# bridge-1A.net
KiCad netlist of a schematic drawn in EAGLE
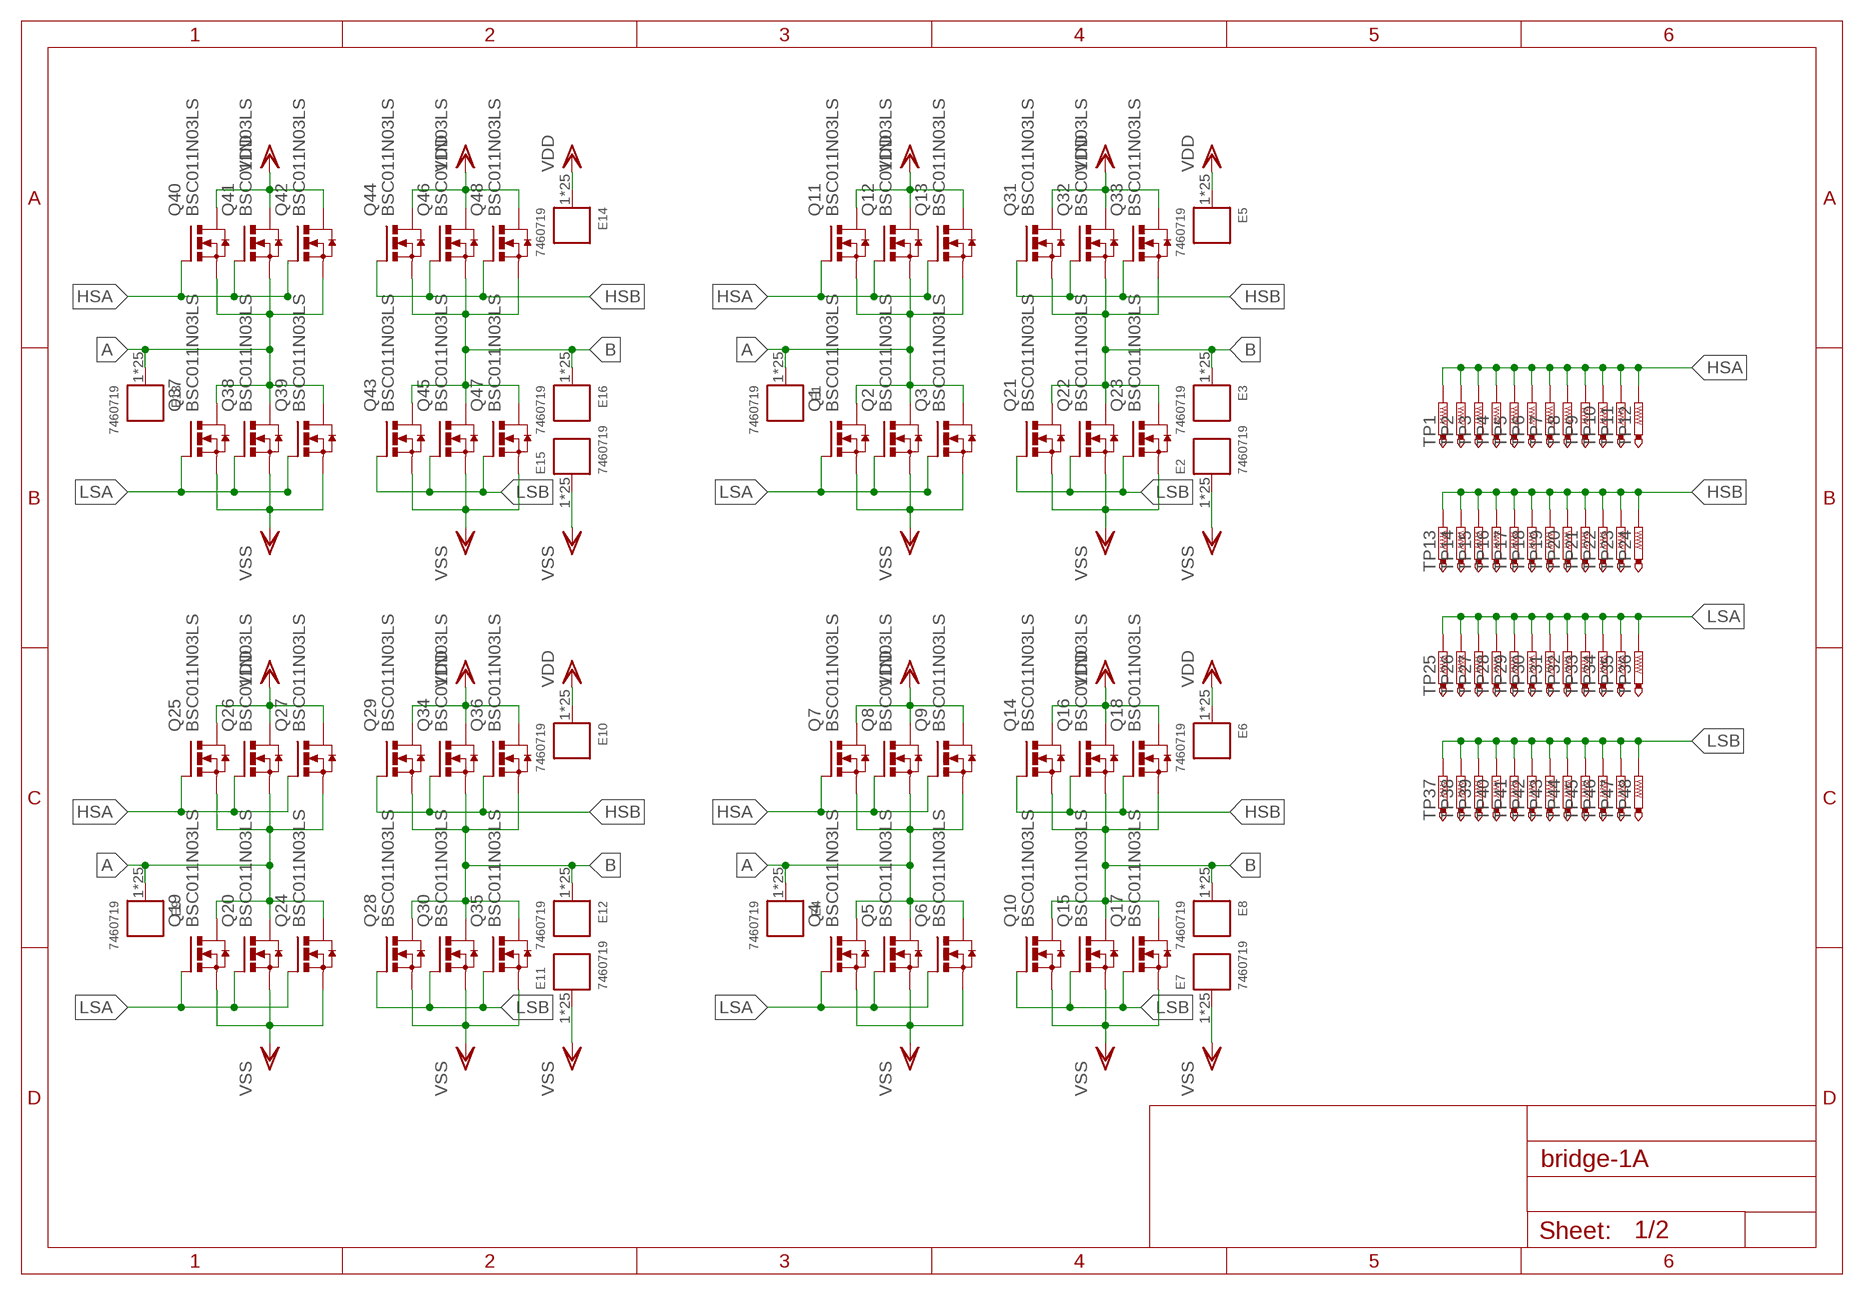
[diagram p0: schematic, sheet 1]

(export (version "E")
  (design (tool "Eeschema 10.0.6"))
  (components
    (comp (ref "E1")
      (value "7460719")
      (footprint "eagle-import:25PINS_FULL_HAL")
      (fields (field (name "MFG") "WUERTHELEKTRONIK"))
      (libsource (lib "eagle-import") (part "WP-SHFU_K(HAL)"))
    )
    (comp (ref "E2")
      (value "7460719")
      (footprint "eagle-import:25PINS_FULL_HAL")
      (fields (field (name "MFG") "WUERTHELEKTRONIK"))
      (libsource (lib "eagle-import") (part "WP-SHFU_K(HAL)"))
    )
    (comp (ref "E3")
      (value "7460719")
      (footprint "eagle-import:25PINS_FULL_HAL")
      (fields (field (name "MFG") "WUERTHELEKTRONIK"))
      (libsource (lib "eagle-import") (part "WP-SHFU_K(HAL)"))
    )
    (comp (ref "E4")
      (value "7460719")
      (footprint "eagle-import:25PINS_FULL_HAL")
      (fields (field (name "MFG") "WUERTHELEKTRONIK"))
      (libsource (lib "eagle-import") (part "WP-SHFU_K(HAL)"))
    )
    (comp (ref "E5")
      (value "7460719")
      (footprint "eagle-import:25PINS_FULL_HAL")
      (fields (field (name "MFG") "WUERTHELEKTRONIK"))
      (libsource (lib "eagle-import") (part "WP-SHFU_K(HAL)"))
    )
    (comp (ref "E6")
      (value "7460719")
      (footprint "eagle-import:25PINS_FULL_HAL")
      (fields (field (name "MFG") "WUERTHELEKTRONIK"))
      (libsource (lib "eagle-import") (part "WP-SHFU_K(HAL)"))
    )
    (comp (ref "E7")
      (value "7460719")
      (footprint "eagle-import:25PINS_FULL_HAL")
      (fields (field (name "MFG") "WUERTHELEKTRONIK"))
      (libsource (lib "eagle-import") (part "WP-SHFU_K(HAL)"))
    )
    (comp (ref "E8")
      (value "7460719")
      (footprint "eagle-import:25PINS_FULL_HAL")
      (fields (field (name "MFG") "WUERTHELEKTRONIK"))
      (libsource (lib "eagle-import") (part "WP-SHFU_K(HAL)"))
    )
    (comp (ref "E9")
      (value "7460719")
      (footprint "eagle-import:25PINS_FULL_HAL")
      (fields (field (name "MFG") "WUERTHELEKTRONIK"))
      (libsource (lib "eagle-import") (part "WP-SHFU_K(HAL)"))
    )
    (comp (ref "E10")
      (value "7460719")
      (footprint "eagle-import:25PINS_FULL_HAL")
      (fields (field (name "MFG") "WUERTHELEKTRONIK"))
      (libsource (lib "eagle-import") (part "WP-SHFU_K(HAL)"))
    )
    (comp (ref "E11")
      (value "7460719")
      (footprint "eagle-import:25PINS_FULL_HAL")
      (fields (field (name "MFG") "WUERTHELEKTRONIK"))
      (libsource (lib "eagle-import") (part "WP-SHFU_K(HAL)"))
    )
    (comp (ref "E12")
      (value "7460719")
      (footprint "eagle-import:25PINS_FULL_HAL")
      (fields (field (name "MFG") "WUERTHELEKTRONIK"))
      (libsource (lib "eagle-import") (part "WP-SHFU_K(HAL)"))
    )
    (comp (ref "E13")
      (value "7460719")
      (footprint "eagle-import:25PINS_FULL_HAL")
      (fields (field (name "MFG") "WUERTHELEKTRONIK"))
      (libsource (lib "eagle-import") (part "WP-SHFU_K(HAL)"))
    )
    (comp (ref "E14")
      (value "7460719")
      (footprint "eagle-import:25PINS_FULL_HAL")
      (fields (field (name "MFG") "WUERTHELEKTRONIK"))
      (libsource (lib "eagle-import") (part "WP-SHFU_K(HAL)"))
    )
    (comp (ref "E15")
      (value "7460719")
      (footprint "eagle-import:25PINS_FULL_HAL")
      (fields (field (name "MFG") "WUERTHELEKTRONIK"))
      (libsource (lib "eagle-import") (part "WP-SHFU_K(HAL)"))
    )
    (comp (ref "E16")
      (value "7460719")
      (footprint "eagle-import:25PINS_FULL_HAL")
      (fields (field (name "MFG") "WUERTHELEKTRONIK"))
      (libsource (lib "eagle-import") (part "WP-SHFU_K(HAL)"))
    )
    (comp (ref "Q1")
      (value "BSC011N03LS")
      (footprint "eagle-import:PG-TDSON-8")
      (libsource (lib "eagle-import") (part "BSC011N03LS"))
    )
    (comp (ref "Q2")
      (value "BSC011N03LS")
      (footprint "eagle-import:PG-TDSON-8")
      (libsource (lib "eagle-import") (part "BSC011N03LS"))
    )
    (comp (ref "Q3")
      (value "BSC011N03LS")
      (footprint "eagle-import:PG-TDSON-8")
      (libsource (lib "eagle-import") (part "BSC011N03LS"))
    )
    (comp (ref "Q4")
      (value "BSC011N03LS")
      (footprint "eagle-import:PG-TDSON-8")
      (libsource (lib "eagle-import") (part "BSC011N03LS"))
    )
    (comp (ref "Q5")
      (value "BSC011N03LS")
      (footprint "eagle-import:PG-TDSON-8")
      (libsource (lib "eagle-import") (part "BSC011N03LS"))
    )
    (comp (ref "Q6")
      (value "BSC011N03LS")
      (footprint "eagle-import:PG-TDSON-8")
      (libsource (lib "eagle-import") (part "BSC011N03LS"))
    )
    (comp (ref "Q7")
      (value "BSC011N03LS")
      (footprint "eagle-import:PG-TDSON-8")
      (libsource (lib "eagle-import") (part "BSC011N03LS"))
    )
    (comp (ref "Q8")
      (value "BSC011N03LS")
      (footprint "eagle-import:PG-TDSON-8")
      (libsource (lib "eagle-import") (part "BSC011N03LS"))
    )
    (comp (ref "Q9")
      (value "BSC011N03LS")
      (footprint "eagle-import:PG-TDSON-8")
      (libsource (lib "eagle-import") (part "BSC011N03LS"))
    )
    (comp (ref "Q10")
      (value "BSC011N03LS")
      (footprint "eagle-import:PG-TDSON-8")
      (libsource (lib "eagle-import") (part "BSC011N03LS"))
    )
    (comp (ref "Q11")
      (value "BSC011N03LS")
      (footprint "eagle-import:PG-TDSON-8")
      (libsource (lib "eagle-import") (part "BSC011N03LS"))
    )
    (comp (ref "Q12")
      (value "BSC011N03LS")
      (footprint "eagle-import:PG-TDSON-8")
      (libsource (lib "eagle-import") (part "BSC011N03LS"))
    )
    (comp (ref "Q13")
      (value "BSC011N03LS")
      (footprint "eagle-import:PG-TDSON-8")
      (libsource (lib "eagle-import") (part "BSC011N03LS"))
    )
    (comp (ref "Q14")
      (value "BSC011N03LS")
      (footprint "eagle-import:PG-TDSON-8")
      (libsource (lib "eagle-import") (part "BSC011N03LS"))
    )
    (comp (ref "Q15")
      (value "BSC011N03LS")
      (footprint "eagle-import:PG-TDSON-8")
      (libsource (lib "eagle-import") (part "BSC011N03LS"))
    )
    (comp (ref "Q16")
      (value "BSC011N03LS")
      (footprint "eagle-import:PG-TDSON-8")
      (libsource (lib "eagle-import") (part "BSC011N03LS"))
    )
    (comp (ref "Q17")
      (value "BSC011N03LS")
      (footprint "eagle-import:PG-TDSON-8")
      (libsource (lib "eagle-import") (part "BSC011N03LS"))
    )
    (comp (ref "Q18")
      (value "BSC011N03LS")
      (footprint "eagle-import:PG-TDSON-8")
      (libsource (lib "eagle-import") (part "BSC011N03LS"))
    )
    (comp (ref "Q19")
      (value "BSC011N03LS")
      (footprint "eagle-import:PG-TDSON-8")
      (libsource (lib "eagle-import") (part "BSC011N03LS"))
    )
    (comp (ref "Q20")
      (value "BSC011N03LS")
      (footprint "eagle-import:PG-TDSON-8")
      (libsource (lib "eagle-import") (part "BSC011N03LS"))
    )
    (comp (ref "Q21")
      (value "BSC011N03LS")
      (footprint "eagle-import:PG-TDSON-8")
      (libsource (lib "eagle-import") (part "BSC011N03LS"))
    )
    (comp (ref "Q22")
      (value "BSC011N03LS")
      (footprint "eagle-import:PG-TDSON-8")
      (libsource (lib "eagle-import") (part "BSC011N03LS"))
    )
    (comp (ref "Q23")
      (value "BSC011N03LS")
      (footprint "eagle-import:PG-TDSON-8")
      (libsource (lib "eagle-import") (part "BSC011N03LS"))
    )
    (comp (ref "Q24")
      (value "BSC011N03LS")
      (footprint "eagle-import:PG-TDSON-8")
      (libsource (lib "eagle-import") (part "BSC011N03LS"))
    )
    (comp (ref "Q25")
      (value "BSC011N03LS")
      (footprint "eagle-import:PG-TDSON-8")
      (libsource (lib "eagle-import") (part "BSC011N03LS"))
    )
    (comp (ref "Q26")
      (value "BSC011N03LS")
      (footprint "eagle-import:PG-TDSON-8")
      (libsource (lib "eagle-import") (part "BSC011N03LS"))
    )
    (comp (ref "Q27")
      (value "BSC011N03LS")
      (footprint "eagle-import:PG-TDSON-8")
      (libsource (lib "eagle-import") (part "BSC011N03LS"))
    )
    (comp (ref "Q28")
      (value "BSC011N03LS")
      (footprint "eagle-import:PG-TDSON-8")
      (libsource (lib "eagle-import") (part "BSC011N03LS"))
    )
    (comp (ref "Q29")
      (value "BSC011N03LS")
      (footprint "eagle-import:PG-TDSON-8")
      (libsource (lib "eagle-import") (part "BSC011N03LS"))
    )
    (comp (ref "Q30")
      (value "BSC011N03LS")
      (footprint "eagle-import:PG-TDSON-8")
      (libsource (lib "eagle-import") (part "BSC011N03LS"))
    )
    (comp (ref "Q31")
      (value "BSC011N03LS")
      (footprint "eagle-import:PG-TDSON-8")
      (libsource (lib "eagle-import") (part "BSC011N03LS"))
    )
    (comp (ref "Q32")
      (value "BSC011N03LS")
      (footprint "eagle-import:PG-TDSON-8")
      (libsource (lib "eagle-import") (part "BSC011N03LS"))
    )
    (comp (ref "Q33")
      (value "BSC011N03LS")
      (footprint "eagle-import:PG-TDSON-8")
      (libsource (lib "eagle-import") (part "BSC011N03LS"))
    )
    (comp (ref "Q34")
      (value "BSC011N03LS")
      (footprint "eagle-import:PG-TDSON-8")
      (libsource (lib "eagle-import") (part "BSC011N03LS"))
    )
    (comp (ref "Q35")
      (value "BSC011N03LS")
      (footprint "eagle-import:PG-TDSON-8")
      (libsource (lib "eagle-import") (part "BSC011N03LS"))
    )
    (comp (ref "Q36")
      (value "BSC011N03LS")
      (footprint "eagle-import:PG-TDSON-8")
      (libsource (lib "eagle-import") (part "BSC011N03LS"))
    )
    (comp (ref "Q37")
      (value "BSC011N03LS")
      (footprint "eagle-import:PG-TDSON-8")
      (libsource (lib "eagle-import") (part "BSC011N03LS"))
    )
    (comp (ref "Q38")
      (value "BSC011N03LS")
      (footprint "eagle-import:PG-TDSON-8")
      (libsource (lib "eagle-import") (part "BSC011N03LS"))
    )
    (comp (ref "Q39")
      (value "BSC011N03LS")
      (footprint "eagle-import:PG-TDSON-8")
      (libsource (lib "eagle-import") (part "BSC011N03LS"))
    )
    (comp (ref "Q40")
      (value "BSC011N03LS")
      (footprint "eagle-import:PG-TDSON-8")
      (libsource (lib "eagle-import") (part "BSC011N03LS"))
    )
    (comp (ref "Q41")
      (value "BSC011N03LS")
      (footprint "eagle-import:PG-TDSON-8")
      (libsource (lib "eagle-import") (part "BSC011N03LS"))
    )
    (comp (ref "Q42")
      (value "BSC011N03LS")
      (footprint "eagle-import:PG-TDSON-8")
      (libsource (lib "eagle-import") (part "BSC011N03LS"))
    )
    (comp (ref "Q43")
      (value "BSC011N03LS")
      (footprint "eagle-import:PG-TDSON-8")
      (libsource (lib "eagle-import") (part "BSC011N03LS"))
    )
    (comp (ref "Q44")
      (value "BSC011N03LS")
      (footprint "eagle-import:PG-TDSON-8")
      (libsource (lib "eagle-import") (part "BSC011N03LS"))
    )
    (comp (ref "Q45")
      (value "BSC011N03LS")
      (footprint "eagle-import:PG-TDSON-8")
      (libsource (lib "eagle-import") (part "BSC011N03LS"))
    )
    (comp (ref "Q46")
      (value "BSC011N03LS")
      (footprint "eagle-import:PG-TDSON-8")
      (libsource (lib "eagle-import") (part "BSC011N03LS"))
    )
    (comp (ref "Q47")
      (value "BSC011N03LS")
      (footprint "eagle-import:PG-TDSON-8")
      (libsource (lib "eagle-import") (part "BSC011N03LS"))
    )
    (comp (ref "Q48")
      (value "BSC011N03LS")
      (footprint "eagle-import:PG-TDSON-8")
      (libsource (lib "eagle-import") (part "BSC011N03LS"))
    )
    (comp (ref "TP1")
      (value "PTR1TP12SQ")
      (footprint "eagle-import:TP12SQ")
      (libsource (lib "eagle-import") (part "PTR1TP12SQ"))
    )
    (comp (ref "TP2")
      (value "PTR1TP12SQ")
      (footprint "eagle-import:TP12SQ")
      (libsource (lib "eagle-import") (part "PTR1TP12SQ"))
    )
    (comp (ref "TP3")
      (value "PTR1TP12SQ")
      (footprint "eagle-import:TP12SQ")
      (libsource (lib "eagle-import") (part "PTR1TP12SQ"))
    )
    (comp (ref "TP4")
      (value "PTR1TP12SQ")
      (footprint "eagle-import:TP12SQ")
      (libsource (lib "eagle-import") (part "PTR1TP12SQ"))
    )
    (comp (ref "TP5")
      (value "PTR1TP12SQ")
      (footprint "eagle-import:TP12SQ")
      (libsource (lib "eagle-import") (part "PTR1TP12SQ"))
    )
    (comp (ref "TP6")
      (value "PTR1TP12SQ")
      (footprint "eagle-import:TP12SQ")
      (libsource (lib "eagle-import") (part "PTR1TP12SQ"))
    )
    (comp (ref "TP7")
      (value "PTR1TP12SQ")
      (footprint "eagle-import:TP12SQ")
      (libsource (lib "eagle-import") (part "PTR1TP12SQ"))
    )
    (comp (ref "TP8")
      (value "PTR1TP12SQ")
      (footprint "eagle-import:TP12SQ")
      (libsource (lib "eagle-import") (part "PTR1TP12SQ"))
    )
    (comp (ref "TP9")
      (value "PTR1TP12SQ")
      (footprint "eagle-import:TP12SQ")
      (libsource (lib "eagle-import") (part "PTR1TP12SQ"))
    )
    (comp (ref "TP10")
      (value "PTR1TP12SQ")
      (footprint "eagle-import:TP12SQ")
      (libsource (lib "eagle-import") (part "PTR1TP12SQ"))
    )
    (comp (ref "TP11")
      (value "PTR1TP12SQ")
      (footprint "eagle-import:TP12SQ")
      (libsource (lib "eagle-import") (part "PTR1TP12SQ"))
    )
    (comp (ref "TP12")
      (value "PTR1TP12SQ")
      (footprint "eagle-import:TP12SQ")
      (libsource (lib "eagle-import") (part "PTR1TP12SQ"))
    )
    (comp (ref "TP13")
      (value "PTR1TP12SQ")
      (footprint "eagle-import:TP12SQ")
      (libsource (lib "eagle-import") (part "PTR1TP12SQ"))
    )
    (comp (ref "TP14")
      (value "PTR1TP12SQ")
      (footprint "eagle-import:TP12SQ")
      (libsource (lib "eagle-import") (part "PTR1TP12SQ"))
    )
    (comp (ref "TP15")
      (value "PTR1TP12SQ")
      (footprint "eagle-import:TP12SQ")
      (libsource (lib "eagle-import") (part "PTR1TP12SQ"))
    )
    (comp (ref "TP16")
      (value "PTR1TP12SQ")
      (footprint "eagle-import:TP12SQ")
      (libsource (lib "eagle-import") (part "PTR1TP12SQ"))
    )
    (comp (ref "TP17")
      (value "PTR1TP12SQ")
      (footprint "eagle-import:TP12SQ")
      (libsource (lib "eagle-import") (part "PTR1TP12SQ"))
    )
    (comp (ref "TP18")
      (value "PTR1TP12SQ")
      (footprint "eagle-import:TP12SQ")
      (libsource (lib "eagle-import") (part "PTR1TP12SQ"))
    )
    (comp (ref "TP19")
      (value "PTR1TP12SQ")
      (footprint "eagle-import:TP12SQ")
      (libsource (lib "eagle-import") (part "PTR1TP12SQ"))
    )
    (comp (ref "TP20")
      (value "PTR1TP12SQ")
      (footprint "eagle-import:TP12SQ")
      (libsource (lib "eagle-import") (part "PTR1TP12SQ"))
    )
    (comp (ref "TP21")
      (value "PTR1TP12SQ")
      (footprint "eagle-import:TP12SQ")
      (libsource (lib "eagle-import") (part "PTR1TP12SQ"))
    )
    (comp (ref "TP22")
      (value "PTR1TP12SQ")
      (footprint "eagle-import:TP12SQ")
      (libsource (lib "eagle-import") (part "PTR1TP12SQ"))
    )
    (comp (ref "TP23")
      (value "PTR1TP12SQ")
      (footprint "eagle-import:TP12SQ")
      (libsource (lib "eagle-import") (part "PTR1TP12SQ"))
    )
    (comp (ref "TP24")
      (value "PTR1TP12SQ")
      (footprint "eagle-import:TP12SQ")
      (libsource (lib "eagle-import") (part "PTR1TP12SQ"))
    )
    (comp (ref "TP25")
      (value "PTR1TP12SQ")
      (footprint "eagle-import:TP12SQ")
      (libsource (lib "eagle-import") (part "PTR1TP12SQ"))
    )
    (comp (ref "TP26")
      (value "PTR1TP12SQ")
      (footprint "eagle-import:TP12SQ")
      (libsource (lib "eagle-import") (part "PTR1TP12SQ"))
    )
    (comp (ref "TP27")
      (value "PTR1TP12SQ")
      (footprint "eagle-import:TP12SQ")
      (libsource (lib "eagle-import") (part "PTR1TP12SQ"))
    )
    (comp (ref "TP28")
      (value "PTR1TP12SQ")
      (footprint "eagle-import:TP12SQ")
      (libsource (lib "eagle-import") (part "PTR1TP12SQ"))
    )
    (comp (ref "TP29")
      (value "PTR1TP12SQ")
      (footprint "eagle-import:TP12SQ")
      (libsource (lib "eagle-import") (part "PTR1TP12SQ"))
    )
    (comp (ref "TP30")
      (value "PTR1TP12SQ")
      (footprint "eagle-import:TP12SQ")
      (libsource (lib "eagle-import") (part "PTR1TP12SQ"))
    )
    (comp (ref "TP31")
      (value "PTR1TP12SQ")
      (footprint "eagle-import:TP12SQ")
      (libsource (lib "eagle-import") (part "PTR1TP12SQ"))
    )
    (comp (ref "TP32")
      (value "PTR1TP12SQ")
      (footprint "eagle-import:TP12SQ")
      (libsource (lib "eagle-import") (part "PTR1TP12SQ"))
    )
    (comp (ref "TP33")
      (value "PTR1TP12SQ")
      (footprint "eagle-import:TP12SQ")
      (libsource (lib "eagle-import") (part "PTR1TP12SQ"))
    )
    (comp (ref "TP34")
      (value "PTR1TP12SQ")
      (footprint "eagle-import:TP12SQ")
      (libsource (lib "eagle-import") (part "PTR1TP12SQ"))
    )
    (comp (ref "TP35")
      (value "PTR1TP12SQ")
      (footprint "eagle-import:TP12SQ")
      (libsource (lib "eagle-import") (part "PTR1TP12SQ"))
    )
    (comp (ref "TP36")
      (value "PTR1TP12SQ")
      (footprint "eagle-import:TP12SQ")
      (libsource (lib "eagle-import") (part "PTR1TP12SQ"))
    )
    (comp (ref "TP37")
      (value "PTR1TP12SQ")
      (footprint "eagle-import:TP12SQ")
      (libsource (lib "eagle-import") (part "PTR1TP12SQ"))
    )
    (comp (ref "TP38")
      (value "PTR1TP12SQ")
      (footprint "eagle-import:TP12SQ")
      (libsource (lib "eagle-import") (part "PTR1TP12SQ"))
    )
    (comp (ref "TP39")
      (value "PTR1TP12SQ")
      (footprint "eagle-import:TP12SQ")
      (libsource (lib "eagle-import") (part "PTR1TP12SQ"))
    )
    (comp (ref "TP40")
      (value "PTR1TP12SQ")
      (footprint "eagle-import:TP12SQ")
      (libsource (lib "eagle-import") (part "PTR1TP12SQ"))
    )
    (comp (ref "TP41")
      (value "PTR1TP12SQ")
      (footprint "eagle-import:TP12SQ")
      (libsource (lib "eagle-import") (part "PTR1TP12SQ"))
    )
    (comp (ref "TP42")
      (value "PTR1TP12SQ")
      (footprint "eagle-import:TP12SQ")
      (libsource (lib "eagle-import") (part "PTR1TP12SQ"))
    )
    (comp (ref "TP43")
      (value "PTR1TP12SQ")
      (footprint "eagle-import:TP12SQ")
      (libsource (lib "eagle-import") (part "PTR1TP12SQ"))
    )
    (comp (ref "TP44")
      (value "PTR1TP12SQ")
      (footprint "eagle-import:TP12SQ")
      (libsource (lib "eagle-import") (part "PTR1TP12SQ"))
    )
    (comp (ref "TP45")
      (value "PTR1TP12SQ")
      (footprint "eagle-import:TP12SQ")
      (libsource (lib "eagle-import") (part "PTR1TP12SQ"))
    )
    (comp (ref "TP46")
      (value "PTR1TP12SQ")
      (footprint "eagle-import:TP12SQ")
      (libsource (lib "eagle-import") (part "PTR1TP12SQ"))
    )
    (comp (ref "TP47")
      (value "PTR1TP12SQ")
      (footprint "eagle-import:TP12SQ")
      (libsource (lib "eagle-import") (part "PTR1TP12SQ"))
    )
    (comp (ref "TP48")
      (value "PTR1TP12SQ")
      (footprint "eagle-import:TP12SQ")
      (libsource (lib "eagle-import") (part "PTR1TP12SQ"))
    )
  )
  (nets
    (net (code "1") (name "A") (class "Default")
      (node (ref "E1") (pin "1") (pinfunction "1_1") (pintype "passive"))
      (node (ref "E1") (pin "10") (pinfunction "1_10") (pintype "passive"))
      (node (ref "E1") (pin "11") (pinfunction "1_11") (pintype "passive"))
      (node (ref "E1") (pin "12") (pinfunction "1_12") (pintype "passive"))
      (node (ref "E1") (pin "13") (pinfunction "1_13") (pintype "passive"))
      (node (ref "E1") (pin "14") (pinfunction "1_14") (pintype "passive"))
      (node (ref "E1") (pin "15") (pinfunction "1_15") (pintype "passive"))
      (node (ref "E1") (pin "16") (pinfunction "1_16") (pintype "passive"))
      (node (ref "E1") (pin "17") (pinfunction "1_17") (pintype "passive"))
      (node (ref "E1") (pin "18") (pinfunction "1_18") (pintype "passive"))
      (node (ref "E1") (pin "19") (pinfunction "1_19") (pintype "passive"))
      (node (ref "E1") (pin "2") (pinfunction "1_2") (pintype "passive"))
      (node (ref "E1") (pin "20") (pinfunction "1_20") (pintype "passive"))
      (node (ref "E1") (pin "21") (pinfunction "1_21") (pintype "passive"))
      (node (ref "E1") (pin "22") (pinfunction "1_22") (pintype "passive"))
      (node (ref "E1") (pin "23") (pinfunction "1_23") (pintype "passive"))
      (node (ref "E1") (pin "24") (pinfunction "1_24") (pintype "passive"))
      (node (ref "E1") (pin "25") (pinfunction "1_25") (pintype "passive"))
      (node (ref "E1") (pin "3") (pinfunction "1_3") (pintype "passive"))
      (node (ref "E1") (pin "4") (pinfunction "1_4") (pintype "passive"))
      (node (ref "E1") (pin "5") (pinfunction "1_5") (pintype "passive"))
      (node (ref "E1") (pin "6") (pinfunction "1_6") (pintype "passive"))
      (node (ref "E1") (pin "7") (pinfunction "1_7") (pintype "passive"))
      (node (ref "E1") (pin "8") (pinfunction "1_8") (pintype "passive"))
      (node (ref "E1") (pin "9") (pinfunction "1_9") (pintype "passive"))
      (node (ref "E13") (pin "1") (pinfunction "1_1") (pintype "passive"))
      (node (ref "E13") (pin "10") (pinfunction "1_10") (pintype "passive"))
      (node (ref "E13") (pin "11") (pinfunction "1_11") (pintype "passive"))
      (node (ref "E13") (pin "12") (pinfunction "1_12") (pintype "passive"))
      (node (ref "E13") (pin "13") (pinfunction "1_13") (pintype "passive"))
      (node (ref "E13") (pin "14") (pinfunction "1_14") (pintype "passive"))
      (node (ref "E13") (pin "15") (pinfunction "1_15") (pintype "passive"))
      (node (ref "E13") (pin "16") (pinfunction "1_16") (pintype "passive"))
      (node (ref "E13") (pin "17") (pinfunction "1_17") (pintype "passive"))
      (node (ref "E13") (pin "18") (pinfunction "1_18") (pintype "passive"))
      (node (ref "E13") (pin "19") (pinfunction "1_19") (pintype "passive"))
      (node (ref "E13") (pin "2") (pinfunction "1_2") (pintype "passive"))
      (node (ref "E13") (pin "20") (pinfunction "1_20") (pintype "passive"))
      (node (ref "E13") (pin "21") (pinfunction "1_21") (pintype "passive"))
      (node (ref "E13") (pin "22") (pinfunction "1_22") (pintype "passive"))
      (node (ref "E13") (pin "23") (pinfunction "1_23") (pintype "passive"))
      (node (ref "E13") (pin "24") (pinfunction "1_24") (pintype "passive"))
      (node (ref "E13") (pin "25") (pinfunction "1_25") (pintype "passive"))
      (node (ref "E13") (pin "3") (pinfunction "1_3") (pintype "passive"))
      (node (ref "E13") (pin "4") (pinfunction "1_4") (pintype "passive"))
      (node (ref "E13") (pin "5") (pinfunction "1_5") (pintype "passive"))
      (node (ref "E13") (pin "6") (pinfunction "1_6") (pintype "passive"))
      (node (ref "E13") (pin "7") (pinfunction "1_7") (pintype "passive"))
      (node (ref "E13") (pin "8") (pinfunction "1_8") (pintype "passive"))
      (node (ref "E13") (pin "9") (pinfunction "1_9") (pintype "passive"))
      (node (ref "E4") (pin "1") (pinfunction "1_1") (pintype "passive"))
      (node (ref "E4") (pin "10") (pinfunction "1_10") (pintype "passive"))
      (node (ref "E4") (pin "11") (pinfunction "1_11") (pintype "passive"))
      (node (ref "E4") (pin "12") (pinfunction "1_12") (pintype "passive"))
      (node (ref "E4") (pin "13") (pinfunction "1_13") (pintype "passive"))
      (node (ref "E4") (pin "14") (pinfunction "1_14") (pintype "passive"))
      (node (ref "E4") (pin "15") (pinfunction "1_15") (pintype "passive"))
      (node (ref "E4") (pin "16") (pinfunction "1_16") (pintype "passive"))
      (node (ref "E4") (pin "17") (pinfunction "1_17") (pintype "passive"))
      (node (ref "E4") (pin "18") (pinfunction "1_18") (pintype "passive"))
      (node (ref "E4") (pin "19") (pinfunction "1_19") (pintype "passive"))
      (node (ref "E4") (pin "2") (pinfunction "1_2") (pintype "passive"))
      (node (ref "E4") (pin "20") (pinfunction "1_20") (pintype "passive"))
      (node (ref "E4") (pin "21") (pinfunction "1_21") (pintype "passive"))
      (node (ref "E4") (pin "22") (pinfunction "1_22") (pintype "passive"))
      (node (ref "E4") (pin "23") (pinfunction "1_23") (pintype "passive"))
      (node (ref "E4") (pin "24") (pinfunction "1_24") (pintype "passive"))
      (node (ref "E4") (pin "25") (pinfunction "1_25") (pintype "passive"))
      (node (ref "E4") (pin "3") (pinfunction "1_3") (pintype "passive"))
      (node (ref "E4") (pin "4") (pinfunction "1_4") (pintype "passive"))
      (node (ref "E4") (pin "5") (pinfunction "1_5") (pintype "passive"))
      (node (ref "E4") (pin "6") (pinfunction "1_6") (pintype "passive"))
      (node (ref "E4") (pin "7") (pinfunction "1_7") (pintype "passive"))
      (node (ref "E4") (pin "8") (pinfunction "1_8") (pintype "passive"))
      (node (ref "E4") (pin "9") (pinfunction "1_9") (pintype "passive"))
      (node (ref "E9") (pin "1") (pinfunction "1_1") (pintype "passive"))
      (node (ref "E9") (pin "10") (pinfunction "1_10") (pintype "passive"))
      (node (ref "E9") (pin "11") (pinfunction "1_11") (pintype "passive"))
      (node (ref "E9") (pin "12") (pinfunction "1_12") (pintype "passive"))
      (node (ref "E9") (pin "13") (pinfunction "1_13") (pintype "passive"))
      (node (ref "E9") (pin "14") (pinfunction "1_14") (pintype "passive"))
      (node (ref "E9") (pin "15") (pinfunction "1_15") (pintype "passive"))
      (node (ref "E9") (pin "16") (pinfunction "1_16") (pintype "passive"))
      (node (ref "E9") (pin "17") (pinfunction "1_17") (pintype "passive"))
      (node (ref "E9") (pin "18") (pinfunction "1_18") (pintype "passive"))
      (node (ref "E9") (pin "19") (pinfunction "1_19") (pintype "passive"))
      (node (ref "E9") (pin "2") (pinfunction "1_2") (pintype "passive"))
      (node (ref "E9") (pin "20") (pinfunction "1_20") (pintype "passive"))
      (node (ref "E9") (pin "21") (pinfunction "1_21") (pintype "passive"))
      (node (ref "E9") (pin "22") (pinfunction "1_22") (pintype "passive"))
      (node (ref "E9") (pin "23") (pinfunction "1_23") (pintype "passive"))
      (node (ref "E9") (pin "24") (pinfunction "1_24") (pintype "passive"))
      (node (ref "E9") (pin "25") (pinfunction "1_25") (pintype "passive"))
      (node (ref "E9") (pin "3") (pinfunction "1_3") (pintype "passive"))
      (node (ref "E9") (pin "4") (pinfunction "1_4") (pintype "passive"))
      (node (ref "E9") (pin "5") (pinfunction "1_5") (pintype "passive"))
      (node (ref "E9") (pin "6") (pinfunction "1_6") (pintype "passive"))
      (node (ref "E9") (pin "7") (pinfunction "1_7") (pintype "passive"))
      (node (ref "E9") (pin "8") (pinfunction "1_8") (pintype "passive"))
      (node (ref "E9") (pin "9") (pinfunction "1_9") (pintype "passive"))
      (node (ref "Q1") (pin "5") (pinfunction "D_5") (pintype "passive"))
      (node (ref "Q1") (pin "6") (pinfunction "D_6") (pintype "passive"))
      (node (ref "Q1") (pin "7") (pinfunction "D_7") (pintype "passive"))
      (node (ref "Q1") (pin "8") (pinfunction "D_8") (pintype "passive"))
      (node (ref "Q1") (pin "TH") (pinfunction "D_TH") (pintype "passive"))
      (node (ref "Q11") (pin "1") (pinfunction "S_1") (pintype "passive"))
      (node (ref "Q11") (pin "2") (pinfunction "S_2") (pintype "passive"))
      (node (ref "Q11") (pin "3") (pinfunction "S_3") (pintype "passive"))
      (node (ref "Q12") (pin "1") (pinfunction "S_1") (pintype "passive"))
      (node (ref "Q12") (pin "2") (pinfunction "S_2") (pintype "passive"))
      (node (ref "Q12") (pin "3") (pinfunction "S_3") (pintype "passive"))
      (node (ref "Q13") (pin "1") (pinfunction "S_1") (pintype "passive"))
      (node (ref "Q13") (pin "2") (pinfunction "S_2") (pintype "passive"))
      (node (ref "Q13") (pin "3") (pinfunction "S_3") (pintype "passive"))
      (node (ref "Q19") (pin "5") (pinfunction "D_5") (pintype "passive"))
      (node (ref "Q19") (pin "6") (pinfunction "D_6") (pintype "passive"))
      (node (ref "Q19") (pin "7") (pinfunction "D_7") (pintype "passive"))
      (node (ref "Q19") (pin "8") (pinfunction "D_8") (pintype "passive"))
      (node (ref "Q19") (pin "TH") (pinfunction "D_TH") (pintype "passive"))
      (node (ref "Q2") (pin "5") (pinfunction "D_5") (pintype "passive"))
      (node (ref "Q2") (pin "6") (pinfunction "D_6") (pintype "passive"))
      (node (ref "Q2") (pin "7") (pinfunction "D_7") (pintype "passive"))
      (node (ref "Q2") (pin "8") (pinfunction "D_8") (pintype "passive"))
      (node (ref "Q2") (pin "TH") (pinfunction "D_TH") (pintype "passive"))
      (node (ref "Q20") (pin "5") (pinfunction "D_5") (pintype "passive"))
      (node (ref "Q20") (pin "6") (pinfunction "D_6") (pintype "passive"))
      (node (ref "Q20") (pin "7") (pinfunction "D_7") (pintype "passive"))
      (node (ref "Q20") (pin "8") (pinfunction "D_8") (pintype "passive"))
      (node (ref "Q20") (pin "TH") (pinfunction "D_TH") (pintype "passive"))
      (node (ref "Q24") (pin "5") (pinfunction "D_5") (pintype "passive"))
      (node (ref "Q24") (pin "6") (pinfunction "D_6") (pintype "passive"))
      (node (ref "Q24") (pin "7") (pinfunction "D_7") (pintype "passive"))
      (node (ref "Q24") (pin "8") (pinfunction "D_8") (pintype "passive"))
      (node (ref "Q24") (pin "TH") (pinfunction "D_TH") (pintype "passive"))
      (node (ref "Q25") (pin "1") (pinfunction "S_1") (pintype "passive"))
      (node (ref "Q25") (pin "2") (pinfunction "S_2") (pintype "passive"))
      (node (ref "Q25") (pin "3") (pinfunction "S_3") (pintype "passive"))
      (node (ref "Q26") (pin "1") (pinfunction "S_1") (pintype "passive"))
      (node (ref "Q26") (pin "2") (pinfunction "S_2") (pintype "passive"))
      (node (ref "Q26") (pin "3") (pinfunction "S_3") (pintype "passive"))
      (node (ref "Q27") (pin "1") (pinfunction "S_1") (pintype "passive"))
      (node (ref "Q27") (pin "2") (pinfunction "S_2") (pintype "passive"))
      (node (ref "Q27") (pin "3") (pinfunction "S_3") (pintype "passive"))
      (node (ref "Q3") (pin "5") (pinfunction "D_5") (pintype "passive"))
      (node (ref "Q3") (pin "6") (pinfunction "D_6") (pintype "passive"))
      (node (ref "Q3") (pin "7") (pinfunction "D_7") (pintype "passive"))
      (node (ref "Q3") (pin "8") (pinfunction "D_8") (pintype "passive"))
      (node (ref "Q3") (pin "TH") (pinfunction "D_TH") (pintype "passive"))
      (node (ref "Q37") (pin "5") (pinfunction "D_5") (pintype "passive"))
      (node (ref "Q37") (pin "6") (pinfunction "D_6") (pintype "passive"))
      (node (ref "Q37") (pin "7") (pinfunction "D_7") (pintype "passive"))
      (node (ref "Q37") (pin "8") (pinfunction "D_8") (pintype "passive"))
      (node (ref "Q37") (pin "TH") (pinfunction "D_TH") (pintype "passive"))
      (node (ref "Q38") (pin "5") (pinfunction "D_5") (pintype "passive"))
      (node (ref "Q38") (pin "6") (pinfunction "D_6") (pintype "passive"))
      (node (ref "Q38") (pin "7") (pinfunction "D_7") (pintype "passive"))
      (node (ref "Q38") (pin "8") (pinfunction "D_8") (pintype "passive"))
      (node (ref "Q38") (pin "TH") (pinfunction "D_TH") (pintype "passive"))
      (node (ref "Q39") (pin "5") (pinfunction "D_5") (pintype "passive"))
      (node (ref "Q39") (pin "6") (pinfunction "D_6") (pintype "passive"))
      (node (ref "Q39") (pin "7") (pinfunction "D_7") (pintype "passive"))
      (node (ref "Q39") (pin "8") (pinfunction "D_8") (pintype "passive"))
      (node (ref "Q39") (pin "TH") (pinfunction "D_TH") (pintype "passive"))
      (node (ref "Q4") (pin "5") (pinfunction "D_5") (pintype "passive"))
      (node (ref "Q4") (pin "6") (pinfunction "D_6") (pintype "passive"))
      (node (ref "Q4") (pin "7") (pinfunction "D_7") (pintype "passive"))
      (node (ref "Q4") (pin "8") (pinfunction "D_8") (pintype "passive"))
      (node (ref "Q4") (pin "TH") (pinfunction "D_TH") (pintype "passive"))
      (node (ref "Q40") (pin "1") (pinfunction "S_1") (pintype "passive"))
      (node (ref "Q40") (pin "2") (pinfunction "S_2") (pintype "passive"))
      (node (ref "Q40") (pin "3") (pinfunction "S_3") (pintype "passive"))
      (node (ref "Q41") (pin "1") (pinfunction "S_1") (pintype "passive"))
      (node (ref "Q41") (pin "2") (pinfunction "S_2") (pintype "passive"))
      (node (ref "Q41") (pin "3") (pinfunction "S_3") (pintype "passive"))
      (node (ref "Q42") (pin "1") (pinfunction "S_1") (pintype "passive"))
      (node (ref "Q42") (pin "2") (pinfunction "S_2") (pintype "passive"))
      (node (ref "Q42") (pin "3") (pinfunction "S_3") (pintype "passive"))
      (node (ref "Q5") (pin "5") (pinfunction "D_5") (pintype "passive"))
      (node (ref "Q5") (pin "6") (pinfunction "D_6") (pintype "passive"))
      (node (ref "Q5") (pin "7") (pinfunction "D_7") (pintype "passive"))
      (node (ref "Q5") (pin "8") (pinfunction "D_8") (pintype "passive"))
      (node (ref "Q5") (pin "TH") (pinfunction "D_TH") (pintype "passive"))
      (node (ref "Q6") (pin "5") (pinfunction "D_5") (pintype "passive"))
      (node (ref "Q6") (pin "6") (pinfunction "D_6") (pintype "passive"))
      (node (ref "Q6") (pin "7") (pinfunction "D_7") (pintype "passive"))
      (node (ref "Q6") (pin "8") (pinfunction "D_8") (pintype "passive"))
      (node (ref "Q6") (pin "TH") (pinfunction "D_TH") (pintype "passive"))
      (node (ref "Q7") (pin "1") (pinfunction "S_1") (pintype "passive"))
      (node (ref "Q7") (pin "2") (pinfunction "S_2") (pintype "passive"))
      (node (ref "Q7") (pin "3") (pinfunction "S_3") (pintype "passive"))
      (node (ref "Q8") (pin "1") (pinfunction "S_1") (pintype "passive"))
      (node (ref "Q8") (pin "2") (pinfunction "S_2") (pintype "passive"))
      (node (ref "Q8") (pin "3") (pinfunction "S_3") (pintype "passive"))
      (node (ref "Q9") (pin "1") (pinfunction "S_1") (pintype "passive"))
      (node (ref "Q9") (pin "2") (pinfunction "S_2") (pintype "passive"))
      (node (ref "Q9") (pin "3") (pinfunction "S_3") (pintype "passive"))
    )
    (net (code "2") (name "B") (class "Default")
      (node (ref "E12") (pin "1") (pinfunction "1_1") (pintype "passive"))
      (node (ref "E12") (pin "10") (pinfunction "1_10") (pintype "passive"))
      (node (ref "E12") (pin "11") (pinfunction "1_11") (pintype "passive"))
      (node (ref "E12") (pin "12") (pinfunction "1_12") (pintype "passive"))
      (node (ref "E12") (pin "13") (pinfunction "1_13") (pintype "passive"))
      (node (ref "E12") (pin "14") (pinfunction "1_14") (pintype "passive"))
      (node (ref "E12") (pin "15") (pinfunction "1_15") (pintype "passive"))
      (node (ref "E12") (pin "16") (pinfunction "1_16") (pintype "passive"))
      (node (ref "E12") (pin "17") (pinfunction "1_17") (pintype "passive"))
      (node (ref "E12") (pin "18") (pinfunction "1_18") (pintype "passive"))
      (node (ref "E12") (pin "19") (pinfunction "1_19") (pintype "passive"))
      (node (ref "E12") (pin "2") (pinfunction "1_2") (pintype "passive"))
      (node (ref "E12") (pin "20") (pinfunction "1_20") (pintype "passive"))
      (node (ref "E12") (pin "21") (pinfunction "1_21") (pintype "passive"))
      (node (ref "E12") (pin "22") (pinfunction "1_22") (pintype "passive"))
      (node (ref "E12") (pin "23") (pinfunction "1_23") (pintype "passive"))
      (node (ref "E12") (pin "24") (pinfunction "1_24") (pintype "passive"))
      (node (ref "E12") (pin "25") (pinfunction "1_25") (pintype "passive"))
      (node (ref "E12") (pin "3") (pinfunction "1_3") (pintype "passive"))
      (node (ref "E12") (pin "4") (pinfunction "1_4") (pintype "passive"))
      (node (ref "E12") (pin "5") (pinfunction "1_5") (pintype "passive"))
      (node (ref "E12") (pin "6") (pinfunction "1_6") (pintype "passive"))
      (node (ref "E12") (pin "7") (pinfunction "1_7") (pintype "passive"))
      (node (ref "E12") (pin "8") (pinfunction "1_8") (pintype "passive"))
      (node (ref "E12") (pin "9") (pinfunction "1_9") (pintype "passive"))
      (node (ref "E16") (pin "1") (pinfunction "1_1") (pintype "passive"))
      (node (ref "E16") (pin "10") (pinfunction "1_10") (pintype "passive"))
      (node (ref "E16") (pin "11") (pinfunction "1_11") (pintype "passive"))
      (node (ref "E16") (pin "12") (pinfunction "1_12") (pintype "passive"))
      (node (ref "E16") (pin "13") (pinfunction "1_13") (pintype "passive"))
      (node (ref "E16") (pin "14") (pinfunction "1_14") (pintype "passive"))
      (node (ref "E16") (pin "15") (pinfunction "1_15") (pintype "passive"))
      (node (ref "E16") (pin "16") (pinfunction "1_16") (pintype "passive"))
      (node (ref "E16") (pin "17") (pinfunction "1_17") (pintype "passive"))
      (node (ref "E16") (pin "18") (pinfunction "1_18") (pintype "passive"))
      (node (ref "E16") (pin "19") (pinfunction "1_19") (pintype "passive"))
      (node (ref "E16") (pin "2") (pinfunction "1_2") (pintype "passive"))
      (node (ref "E16") (pin "20") (pinfunction "1_20") (pintype "passive"))
      (node (ref "E16") (pin "21") (pinfunction "1_21") (pintype "passive"))
      (node (ref "E16") (pin "22") (pinfunction "1_22") (pintype "passive"))
      (node (ref "E16") (pin "23") (pinfunction "1_23") (pintype "passive"))
      (node (ref "E16") (pin "24") (pinfunction "1_24") (pintype "passive"))
      (node (ref "E16") (pin "25") (pinfunction "1_25") (pintype "passive"))
      (node (ref "E16") (pin "3") (pinfunction "1_3") (pintype "passive"))
      (node (ref "E16") (pin "4") (pinfunction "1_4") (pintype "passive"))
      (node (ref "E16") (pin "5") (pinfunction "1_5") (pintype "passive"))
      (node (ref "E16") (pin "6") (pinfunction "1_6") (pintype "passive"))
      (node (ref "E16") (pin "7") (pinfunction "1_7") (pintype "passive"))
      (node (ref "E16") (pin "8") (pinfunction "1_8") (pintype "passive"))
      (node (ref "E16") (pin "9") (pinfunction "1_9") (pintype "passive"))
      (node (ref "E3") (pin "1") (pinfunction "1_1") (pintype "passive"))
      (node (ref "E3") (pin "10") (pinfunction "1_10") (pintype "passive"))
      (node (ref "E3") (pin "11") (pinfunction "1_11") (pintype "passive"))
      (node (ref "E3") (pin "12") (pinfunction "1_12") (pintype "passive"))
      (node (ref "E3") (pin "13") (pinfunction "1_13") (pintype "passive"))
      (node (ref "E3") (pin "14") (pinfunction "1_14") (pintype "passive"))
      (node (ref "E3") (pin "15") (pinfunction "1_15") (pintype "passive"))
      (node (ref "E3") (pin "16") (pinfunction "1_16") (pintype "passive"))
      (node (ref "E3") (pin "17") (pinfunction "1_17") (pintype "passive"))
      (node (ref "E3") (pin "18") (pinfunction "1_18") (pintype "passive"))
      (node (ref "E3") (pin "19") (pinfunction "1_19") (pintype "passive"))
      (node (ref "E3") (pin "2") (pinfunction "1_2") (pintype "passive"))
      (node (ref "E3") (pin "20") (pinfunction "1_20") (pintype "passive"))
      (node (ref "E3") (pin "21") (pinfunction "1_21") (pintype "passive"))
      (node (ref "E3") (pin "22") (pinfunction "1_22") (pintype "passive"))
      (node (ref "E3") (pin "23") (pinfunction "1_23") (pintype "passive"))
      (node (ref "E3") (pin "24") (pinfunction "1_24") (pintype "passive"))
      (node (ref "E3") (pin "25") (pinfunction "1_25") (pintype "passive"))
      (node (ref "E3") (pin "3") (pinfunction "1_3") (pintype "passive"))
      (node (ref "E3") (pin "4") (pinfunction "1_4") (pintype "passive"))
      (node (ref "E3") (pin "5") (pinfunction "1_5") (pintype "passive"))
      (node (ref "E3") (pin "6") (pinfunction "1_6") (pintype "passive"))
      (node (ref "E3") (pin "7") (pinfunction "1_7") (pintype "passive"))
      (node (ref "E3") (pin "8") (pinfunction "1_8") (pintype "passive"))
      (node (ref "E3") (pin "9") (pinfunction "1_9") (pintype "passive"))
      (node (ref "E8") (pin "1") (pinfunction "1_1") (pintype "passive"))
      (node (ref "E8") (pin "10") (pinfunction "1_10") (pintype "passive"))
      (node (ref "E8") (pin "11") (pinfunction "1_11") (pintype "passive"))
      (node (ref "E8") (pin "12") (pinfunction "1_12") (pintype "passive"))
      (node (ref "E8") (pin "13") (pinfunction "1_13") (pintype "passive"))
      (node (ref "E8") (pin "14") (pinfunction "1_14") (pintype "passive"))
      (node (ref "E8") (pin "15") (pinfunction "1_15") (pintype "passive"))
      (node (ref "E8") (pin "16") (pinfunction "1_16") (pintype "passive"))
      (node (ref "E8") (pin "17") (pinfunction "1_17") (pintype "passive"))
      (node (ref "E8") (pin "18") (pinfunction "1_18") (pintype "passive"))
      (node (ref "E8") (pin "19") (pinfunction "1_19") (pintype "passive"))
      (node (ref "E8") (pin "2") (pinfunction "1_2") (pintype "passive"))
      (node (ref "E8") (pin "20") (pinfunction "1_20") (pintype "passive"))
      (node (ref "E8") (pin "21") (pinfunction "1_21") (pintype "passive"))
      (node (ref "E8") (pin "22") (pinfunction "1_22") (pintype "passive"))
      (node (ref "E8") (pin "23") (pinfunction "1_23") (pintype "passive"))
      (node (ref "E8") (pin "24") (pinfunction "1_24") (pintype "passive"))
      (node (ref "E8") (pin "25") (pinfunction "1_25") (pintype "passive"))
      (node (ref "E8") (pin "3") (pinfunction "1_3") (pintype "passive"))
      (node (ref "E8") (pin "4") (pinfunction "1_4") (pintype "passive"))
      (node (ref "E8") (pin "5") (pinfunction "1_5") (pintype "passive"))
      (node (ref "E8") (pin "6") (pinfunction "1_6") (pintype "passive"))
      (node (ref "E8") (pin "7") (pinfunction "1_7") (pintype "passive"))
      (node (ref "E8") (pin "8") (pinfunction "1_8") (pintype "passive"))
      (node (ref "E8") (pin "9") (pinfunction "1_9") (pintype "passive"))
      (node (ref "Q10") (pin "5") (pinfunction "D_5") (pintype "passive"))
      (node (ref "Q10") (pin "6") (pinfunction "D_6") (pintype "passive"))
      (node (ref "Q10") (pin "7") (pinfunction "D_7") (pintype "passive"))
      (node (ref "Q10") (pin "8") (pinfunction "D_8") (pintype "passive"))
      (node (ref "Q10") (pin "TH") (pinfunction "D_TH") (pintype "passive"))
      (node (ref "Q14") (pin "1") (pinfunction "S_1") (pintype "passive"))
      (node (ref "Q14") (pin "2") (pinfunction "S_2") (pintype "passive"))
      (node (ref "Q14") (pin "3") (pinfunction "S_3") (pintype "passive"))
      (node (ref "Q15") (pin "5") (pinfunction "D_5") (pintype "passive"))
      (node (ref "Q15") (pin "6") (pinfunction "D_6") (pintype "passive"))
      (node (ref "Q15") (pin "7") (pinfunction "D_7") (pintype "passive"))
      (node (ref "Q15") (pin "8") (pinfunction "D_8") (pintype "passive"))
      (node (ref "Q15") (pin "TH") (pinfunction "D_TH") (pintype "passive"))
      (node (ref "Q16") (pin "1") (pinfunction "S_1") (pintype "passive"))
      (node (ref "Q16") (pin "2") (pinfunction "S_2") (pintype "passive"))
      (node (ref "Q16") (pin "3") (pinfunction "S_3") (pintype "passive"))
      (node (ref "Q17") (pin "5") (pinfunction "D_5") (pintype "passive"))
      (node (ref "Q17") (pin "6") (pinfunction "D_6") (pintype "passive"))
      (node (ref "Q17") (pin "7") (pinfunction "D_7") (pintype "passive"))
      (node (ref "Q17") (pin "8") (pinfunction "D_8") (pintype "passive"))
      (node (ref "Q17") (pin "TH") (pinfunction "D_TH") (pintype "passive"))
      (node (ref "Q18") (pin "1") (pinfunction "S_1") (pintype "passive"))
      (node (ref "Q18") (pin "2") (pinfunction "S_2") (pintype "passive"))
      (node (ref "Q18") (pin "3") (pinfunction "S_3") (pintype "passive"))
      (node (ref "Q21") (pin "5") (pinfunction "D_5") (pintype "passive"))
      (node (ref "Q21") (pin "6") (pinfunction "D_6") (pintype "passive"))
      (node (ref "Q21") (pin "7") (pinfunction "D_7") (pintype "passive"))
      (node (ref "Q21") (pin "8") (pinfunction "D_8") (pintype "passive"))
      (node (ref "Q21") (pin "TH") (pinfunction "D_TH") (pintype "passive"))
      (node (ref "Q22") (pin "5") (pinfunction "D_5") (pintype "passive"))
      (node (ref "Q22") (pin "6") (pinfunction "D_6") (pintype "passive"))
      (node (ref "Q22") (pin "7") (pinfunction "D_7") (pintype "passive"))
      (node (ref "Q22") (pin "8") (pinfunction "D_8") (pintype "passive"))
      (node (ref "Q22") (pin "TH") (pinfunction "D_TH") (pintype "passive"))
      (node (ref "Q23") (pin "5") (pinfunction "D_5") (pintype "passive"))
      (node (ref "Q23") (pin "6") (pinfunction "D_6") (pintype "passive"))
      (node (ref "Q23") (pin "7") (pinfunction "D_7") (pintype "passive"))
      (node (ref "Q23") (pin "8") (pinfunction "D_8") (pintype "passive"))
      (node (ref "Q23") (pin "TH") (pinfunction "D_TH") (pintype "passive"))
      (node (ref "Q28") (pin "5") (pinfunction "D_5") (pintype "passive"))
      (node (ref "Q28") (pin "6") (pinfunction "D_6") (pintype "passive"))
      (node (ref "Q28") (pin "7") (pinfunction "D_7") (pintype "passive"))
      (node (ref "Q28") (pin "8") (pinfunction "D_8") (pintype "passive"))
      (node (ref "Q28") (pin "TH") (pinfunction "D_TH") (pintype "passive"))
      (node (ref "Q29") (pin "1") (pinfunction "S_1") (pintype "passive"))
      (node (ref "Q29") (pin "2") (pinfunction "S_2") (pintype "passive"))
      (node (ref "Q29") (pin "3") (pinfunction "S_3") (pintype "passive"))
      (node (ref "Q30") (pin "5") (pinfunction "D_5") (pintype "passive"))
      (node (ref "Q30") (pin "6") (pinfunction "D_6") (pintype "passive"))
      (node (ref "Q30") (pin "7") (pinfunction "D_7") (pintype "passive"))
      (node (ref "Q30") (pin "8") (pinfunction "D_8") (pintype "passive"))
      (node (ref "Q30") (pin "TH") (pinfunction "D_TH") (pintype "passive"))
      (node (ref "Q31") (pin "1") (pinfunction "S_1") (pintype "passive"))
      (node (ref "Q31") (pin "2") (pinfunction "S_2") (pintype "passive"))
      (node (ref "Q31") (pin "3") (pinfunction "S_3") (pintype "passive"))
      (node (ref "Q32") (pin "1") (pinfunction "S_1") (pintype "passive"))
      (node (ref "Q32") (pin "2") (pinfunction "S_2") (pintype "passive"))
      (node (ref "Q32") (pin "3") (pinfunction "S_3") (pintype "passive"))
      (node (ref "Q33") (pin "1") (pinfunction "S_1") (pintype "passive"))
      (node (ref "Q33") (pin "2") (pinfunction "S_2") (pintype "passive"))
      (node (ref "Q33") (pin "3") (pinfunction "S_3") (pintype "passive"))
      (node (ref "Q34") (pin "1") (pinfunction "S_1") (pintype "passive"))
      (node (ref "Q34") (pin "2") (pinfunction "S_2") (pintype "passive"))
      (node (ref "Q34") (pin "3") (pinfunction "S_3") (pintype "passive"))
      (node (ref "Q35") (pin "5") (pinfunction "D_5") (pintype "passive"))
      (node (ref "Q35") (pin "6") (pinfunction "D_6") (pintype "passive"))
      (node (ref "Q35") (pin "7") (pinfunction "D_7") (pintype "passive"))
      (node (ref "Q35") (pin "8") (pinfunction "D_8") (pintype "passive"))
      (node (ref "Q35") (pin "TH") (pinfunction "D_TH") (pintype "passive"))
      (node (ref "Q36") (pin "1") (pinfunction "S_1") (pintype "passive"))
      (node (ref "Q36") (pin "2") (pinfunction "S_2") (pintype "passive"))
      (node (ref "Q36") (pin "3") (pinfunction "S_3") (pintype "passive"))
      (node (ref "Q43") (pin "5") (pinfunction "D_5") (pintype "passive"))
      (node (ref "Q43") (pin "6") (pinfunction "D_6") (pintype "passive"))
      (node (ref "Q43") (pin "7") (pinfunction "D_7") (pintype "passive"))
      (node (ref "Q43") (pin "8") (pinfunction "D_8") (pintype "passive"))
      (node (ref "Q43") (pin "TH") (pinfunction "D_TH") (pintype "passive"))
      (node (ref "Q44") (pin "1") (pinfunction "S_1") (pintype "passive"))
      (node (ref "Q44") (pin "2") (pinfunction "S_2") (pintype "passive"))
      (node (ref "Q44") (pin "3") (pinfunction "S_3") (pintype "passive"))
      (node (ref "Q45") (pin "5") (pinfunction "D_5") (pintype "passive"))
      (node (ref "Q45") (pin "6") (pinfunction "D_6") (pintype "passive"))
      (node (ref "Q45") (pin "7") (pinfunction "D_7") (pintype "passive"))
      (node (ref "Q45") (pin "8") (pinfunction "D_8") (pintype "passive"))
      (node (ref "Q45") (pin "TH") (pinfunction "D_TH") (pintype "passive"))
      (node (ref "Q46") (pin "1") (pinfunction "S_1") (pintype "passive"))
      (node (ref "Q46") (pin "2") (pinfunction "S_2") (pintype "passive"))
      (node (ref "Q46") (pin "3") (pinfunction "S_3") (pintype "passive"))
      (node (ref "Q47") (pin "5") (pinfunction "D_5") (pintype "passive"))
      (node (ref "Q47") (pin "6") (pinfunction "D_6") (pintype "passive"))
      (node (ref "Q47") (pin "7") (pinfunction "D_7") (pintype "passive"))
      (node (ref "Q47") (pin "8") (pinfunction "D_8") (pintype "passive"))
      (node (ref "Q47") (pin "TH") (pinfunction "D_TH") (pintype "passive"))
      (node (ref "Q48") (pin "1") (pinfunction "S_1") (pintype "passive"))
      (node (ref "Q48") (pin "2") (pinfunction "S_2") (pintype "passive"))
      (node (ref "Q48") (pin "3") (pinfunction "S_3") (pintype "passive"))
    )
    (net (code "3") (name "HSA") (class "Default")
      (node (ref "Q11") (pin "4") (pinfunction "G_4") (pintype "passive"))
      (node (ref "Q12") (pin "4") (pinfunction "G_4") (pintype "passive"))
      (node (ref "Q13") (pin "4") (pinfunction "G_4") (pintype "passive"))
      (node (ref "Q25") (pin "4") (pinfunction "G_4") (pintype "passive"))
      (node (ref "Q26") (pin "4") (pinfunction "G_4") (pintype "passive"))
      (node (ref "Q27") (pin "4") (pinfunction "G_4") (pintype "passive"))
      (node (ref "Q40") (pin "4") (pinfunction "G_4") (pintype "passive"))
      (node (ref "Q41") (pin "4") (pinfunction "G_4") (pintype "passive"))
      (node (ref "Q42") (pin "4") (pinfunction "G_4") (pintype "passive"))
      (node (ref "Q7") (pin "4") (pinfunction "G_4") (pintype "passive"))
      (node (ref "Q8") (pin "4") (pinfunction "G_4") (pintype "passive"))
      (node (ref "Q9") (pin "4") (pinfunction "G_4") (pintype "passive"))
      (node (ref "TP1") (pin "TP") (pinfunction "TP_TP") (pintype "input"))
      (node (ref "TP10") (pin "TP") (pinfunction "TP_TP") (pintype "input"))
      (node (ref "TP11") (pin "TP") (pinfunction "TP_TP") (pintype "input"))
      (node (ref "TP12") (pin "TP") (pinfunction "TP_TP") (pintype "input"))
      (node (ref "TP2") (pin "TP") (pinfunction "TP_TP") (pintype "input"))
      (node (ref "TP3") (pin "TP") (pinfunction "TP_TP") (pintype "input"))
      (node (ref "TP4") (pin "TP") (pinfunction "TP_TP") (pintype "input"))
      (node (ref "TP5") (pin "TP") (pinfunction "TP_TP") (pintype "input"))
      (node (ref "TP6") (pin "TP") (pinfunction "TP_TP") (pintype "input"))
      (node (ref "TP7") (pin "TP") (pinfunction "TP_TP") (pintype "input"))
      (node (ref "TP8") (pin "TP") (pinfunction "TP_TP") (pintype "input"))
      (node (ref "TP9") (pin "TP") (pinfunction "TP_TP") (pintype "input"))
    )
    (net (code "4") (name "HSB") (class "Default")
      (node (ref "Q14") (pin "4") (pinfunction "G_4") (pintype "passive"))
      (node (ref "Q16") (pin "4") (pinfunction "G_4") (pintype "passive"))
      (node (ref "Q18") (pin "4") (pinfunction "G_4") (pintype "passive"))
      (node (ref "Q29") (pin "4") (pinfunction "G_4") (pintype "passive"))
      (node (ref "Q31") (pin "4") (pinfunction "G_4") (pintype "passive"))
      (node (ref "Q32") (pin "4") (pinfunction "G_4") (pintype "passive"))
      (node (ref "Q33") (pin "4") (pinfunction "G_4") (pintype "passive"))
      (node (ref "Q34") (pin "4") (pinfunction "G_4") (pintype "passive"))
      (node (ref "Q36") (pin "4") (pinfunction "G_4") (pintype "passive"))
      (node (ref "Q44") (pin "4") (pinfunction "G_4") (pintype "passive"))
      (node (ref "Q46") (pin "4") (pinfunction "G_4") (pintype "passive"))
      (node (ref "Q48") (pin "4") (pinfunction "G_4") (pintype "passive"))
      (node (ref "TP13") (pin "TP") (pinfunction "TP_TP") (pintype "input"))
      (node (ref "TP14") (pin "TP") (pinfunction "TP_TP") (pintype "input"))
      (node (ref "TP15") (pin "TP") (pinfunction "TP_TP") (pintype "input"))
      (node (ref "TP16") (pin "TP") (pinfunction "TP_TP") (pintype "input"))
      (node (ref "TP17") (pin "TP") (pinfunction "TP_TP") (pintype "input"))
      (node (ref "TP18") (pin "TP") (pinfunction "TP_TP") (pintype "input"))
      (node (ref "TP19") (pin "TP") (pinfunction "TP_TP") (pintype "input"))
      (node (ref "TP20") (pin "TP") (pinfunction "TP_TP") (pintype "input"))
      (node (ref "TP21") (pin "TP") (pinfunction "TP_TP") (pintype "input"))
      (node (ref "TP22") (pin "TP") (pinfunction "TP_TP") (pintype "input"))
      (node (ref "TP23") (pin "TP") (pinfunction "TP_TP") (pintype "input"))
      (node (ref "TP24") (pin "TP") (pinfunction "TP_TP") (pintype "input"))
    )
    (net (code "5") (name "LSA") (class "Default")
      (node (ref "Q1") (pin "4") (pinfunction "G_4") (pintype "passive"))
      (node (ref "Q19") (pin "4") (pinfunction "G_4") (pintype "passive"))
      (node (ref "Q2") (pin "4") (pinfunction "G_4") (pintype "passive"))
      (node (ref "Q20") (pin "4") (pinfunction "G_4") (pintype "passive"))
      (node (ref "Q24") (pin "4") (pinfunction "G_4") (pintype "passive"))
      (node (ref "Q3") (pin "4") (pinfunction "G_4") (pintype "passive"))
      (node (ref "Q37") (pin "4") (pinfunction "G_4") (pintype "passive"))
      (node (ref "Q38") (pin "4") (pinfunction "G_4") (pintype "passive"))
      (node (ref "Q39") (pin "4") (pinfunction "G_4") (pintype "passive"))
      (node (ref "Q4") (pin "4") (pinfunction "G_4") (pintype "passive"))
      (node (ref "Q5") (pin "4") (pinfunction "G_4") (pintype "passive"))
      (node (ref "Q6") (pin "4") (pinfunction "G_4") (pintype "passive"))
      (node (ref "TP25") (pin "TP") (pinfunction "TP_TP") (pintype "input"))
      (node (ref "TP26") (pin "TP") (pinfunction "TP_TP") (pintype "input"))
      (node (ref "TP27") (pin "TP") (pinfunction "TP_TP") (pintype "input"))
      (node (ref "TP28") (pin "TP") (pinfunction "TP_TP") (pintype "input"))
      (node (ref "TP29") (pin "TP") (pinfunction "TP_TP") (pintype "input"))
      (node (ref "TP30") (pin "TP") (pinfunction "TP_TP") (pintype "input"))
      (node (ref "TP31") (pin "TP") (pinfunction "TP_TP") (pintype "input"))
      (node (ref "TP32") (pin "TP") (pinfunction "TP_TP") (pintype "input"))
      (node (ref "TP33") (pin "TP") (pinfunction "TP_TP") (pintype "input"))
      (node (ref "TP34") (pin "TP") (pinfunction "TP_TP") (pintype "input"))
      (node (ref "TP35") (pin "TP") (pinfunction "TP_TP") (pintype "input"))
      (node (ref "TP36") (pin "TP") (pinfunction "TP_TP") (pintype "input"))
    )
    (net (code "6") (name "LSB") (class "Default")
      (node (ref "Q10") (pin "4") (pinfunction "G_4") (pintype "passive"))
      (node (ref "Q15") (pin "4") (pinfunction "G_4") (pintype "passive"))
      (node (ref "Q17") (pin "4") (pinfunction "G_4") (pintype "passive"))
      (node (ref "Q21") (pin "4") (pinfunction "G_4") (pintype "passive"))
      (node (ref "Q22") (pin "4") (pinfunction "G_4") (pintype "passive"))
      (node (ref "Q23") (pin "4") (pinfunction "G_4") (pintype "passive"))
      (node (ref "Q28") (pin "4") (pinfunction "G_4") (pintype "passive"))
      (node (ref "Q30") (pin "4") (pinfunction "G_4") (pintype "passive"))
      (node (ref "Q35") (pin "4") (pinfunction "G_4") (pintype "passive"))
      (node (ref "Q43") (pin "4") (pinfunction "G_4") (pintype "passive"))
      (node (ref "Q45") (pin "4") (pinfunction "G_4") (pintype "passive"))
      (node (ref "Q47") (pin "4") (pinfunction "G_4") (pintype "passive"))
      (node (ref "TP37") (pin "TP") (pinfunction "TP_TP") (pintype "input"))
      (node (ref "TP38") (pin "TP") (pinfunction "TP_TP") (pintype "input"))
      (node (ref "TP39") (pin "TP") (pinfunction "TP_TP") (pintype "input"))
      (node (ref "TP40") (pin "TP") (pinfunction "TP_TP") (pintype "input"))
      (node (ref "TP41") (pin "TP") (pinfunction "TP_TP") (pintype "input"))
      (node (ref "TP42") (pin "TP") (pinfunction "TP_TP") (pintype "input"))
      (node (ref "TP43") (pin "TP") (pinfunction "TP_TP") (pintype "input"))
      (node (ref "TP44") (pin "TP") (pinfunction "TP_TP") (pintype "input"))
      (node (ref "TP45") (pin "TP") (pinfunction "TP_TP") (pintype "input"))
      (node (ref "TP46") (pin "TP") (pinfunction "TP_TP") (pintype "input"))
      (node (ref "TP47") (pin "TP") (pinfunction "TP_TP") (pintype "input"))
      (node (ref "TP48") (pin "TP") (pinfunction "TP_TP") (pintype "input"))
    )
    (net (code "7") (name "VDD") (class "Default")
      (node (ref "E10") (pin "1") (pinfunction "1_1") (pintype "passive"))
      (node (ref "E10") (pin "10") (pinfunction "1_10") (pintype "passive"))
      (node (ref "E10") (pin "11") (pinfunction "1_11") (pintype "passive"))
      (node (ref "E10") (pin "12") (pinfunction "1_12") (pintype "passive"))
      (node (ref "E10") (pin "13") (pinfunction "1_13") (pintype "passive"))
      (node (ref "E10") (pin "14") (pinfunction "1_14") (pintype "passive"))
      (node (ref "E10") (pin "15") (pinfunction "1_15") (pintype "passive"))
      (node (ref "E10") (pin "16") (pinfunction "1_16") (pintype "passive"))
      (node (ref "E10") (pin "17") (pinfunction "1_17") (pintype "passive"))
      (node (ref "E10") (pin "18") (pinfunction "1_18") (pintype "passive"))
      (node (ref "E10") (pin "19") (pinfunction "1_19") (pintype "passive"))
      (node (ref "E10") (pin "2") (pinfunction "1_2") (pintype "passive"))
      (node (ref "E10") (pin "20") (pinfunction "1_20") (pintype "passive"))
      (node (ref "E10") (pin "21") (pinfunction "1_21") (pintype "passive"))
      (node (ref "E10") (pin "22") (pinfunction "1_22") (pintype "passive"))
      (node (ref "E10") (pin "23") (pinfunction "1_23") (pintype "passive"))
      (node (ref "E10") (pin "24") (pinfunction "1_24") (pintype "passive"))
      (node (ref "E10") (pin "25") (pinfunction "1_25") (pintype "passive"))
      (node (ref "E10") (pin "3") (pinfunction "1_3") (pintype "passive"))
      (node (ref "E10") (pin "4") (pinfunction "1_4") (pintype "passive"))
      (node (ref "E10") (pin "5") (pinfunction "1_5") (pintype "passive"))
      (node (ref "E10") (pin "6") (pinfunction "1_6") (pintype "passive"))
      (node (ref "E10") (pin "7") (pinfunction "1_7") (pintype "passive"))
      (node (ref "E10") (pin "8") (pinfunction "1_8") (pintype "passive"))
      (node (ref "E10") (pin "9") (pinfunction "1_9") (pintype "passive"))
      (node (ref "E14") (pin "1") (pinfunction "1_1") (pintype "passive"))
      (node (ref "E14") (pin "10") (pinfunction "1_10") (pintype "passive"))
      (node (ref "E14") (pin "11") (pinfunction "1_11") (pintype "passive"))
      (node (ref "E14") (pin "12") (pinfunction "1_12") (pintype "passive"))
      (node (ref "E14") (pin "13") (pinfunction "1_13") (pintype "passive"))
      (node (ref "E14") (pin "14") (pinfunction "1_14") (pintype "passive"))
      (node (ref "E14") (pin "15") (pinfunction "1_15") (pintype "passive"))
      (node (ref "E14") (pin "16") (pinfunction "1_16") (pintype "passive"))
      (node (ref "E14") (pin "17") (pinfunction "1_17") (pintype "passive"))
      (node (ref "E14") (pin "18") (pinfunction "1_18") (pintype "passive"))
      (node (ref "E14") (pin "19") (pinfunction "1_19") (pintype "passive"))
      (node (ref "E14") (pin "2") (pinfunction "1_2") (pintype "passive"))
      (node (ref "E14") (pin "20") (pinfunction "1_20") (pintype "passive"))
      (node (ref "E14") (pin "21") (pinfunction "1_21") (pintype "passive"))
      (node (ref "E14") (pin "22") (pinfunction "1_22") (pintype "passive"))
      (node (ref "E14") (pin "23") (pinfunction "1_23") (pintype "passive"))
      (node (ref "E14") (pin "24") (pinfunction "1_24") (pintype "passive"))
      (node (ref "E14") (pin "25") (pinfunction "1_25") (pintype "passive"))
      (node (ref "E14") (pin "3") (pinfunction "1_3") (pintype "passive"))
      (node (ref "E14") (pin "4") (pinfunction "1_4") (pintype "passive"))
      (node (ref "E14") (pin "5") (pinfunction "1_5") (pintype "passive"))
      (node (ref "E14") (pin "6") (pinfunction "1_6") (pintype "passive"))
      (node (ref "E14") (pin "7") (pinfunction "1_7") (pintype "passive"))
      (node (ref "E14") (pin "8") (pinfunction "1_8") (pintype "passive"))
      (node (ref "E14") (pin "9") (pinfunction "1_9") (pintype "passive"))
      (node (ref "E5") (pin "1") (pinfunction "1_1") (pintype "passive"))
      (node (ref "E5") (pin "10") (pinfunction "1_10") (pintype "passive"))
      (node (ref "E5") (pin "11") (pinfunction "1_11") (pintype "passive"))
      (node (ref "E5") (pin "12") (pinfunction "1_12") (pintype "passive"))
      (node (ref "E5") (pin "13") (pinfunction "1_13") (pintype "passive"))
      (node (ref "E5") (pin "14") (pinfunction "1_14") (pintype "passive"))
      (node (ref "E5") (pin "15") (pinfunction "1_15") (pintype "passive"))
      (node (ref "E5") (pin "16") (pinfunction "1_16") (pintype "passive"))
      (node (ref "E5") (pin "17") (pinfunction "1_17") (pintype "passive"))
      (node (ref "E5") (pin "18") (pinfunction "1_18") (pintype "passive"))
      (node (ref "E5") (pin "19") (pinfunction "1_19") (pintype "passive"))
      (node (ref "E5") (pin "2") (pinfunction "1_2") (pintype "passive"))
      (node (ref "E5") (pin "20") (pinfunction "1_20") (pintype "passive"))
      (node (ref "E5") (pin "21") (pinfunction "1_21") (pintype "passive"))
      (node (ref "E5") (pin "22") (pinfunction "1_22") (pintype "passive"))
      (node (ref "E5") (pin "23") (pinfunction "1_23") (pintype "passive"))
      (node (ref "E5") (pin "24") (pinfunction "1_24") (pintype "passive"))
      (node (ref "E5") (pin "25") (pinfunction "1_25") (pintype "passive"))
      (node (ref "E5") (pin "3") (pinfunction "1_3") (pintype "passive"))
      (node (ref "E5") (pin "4") (pinfunction "1_4") (pintype "passive"))
      (node (ref "E5") (pin "5") (pinfunction "1_5") (pintype "passive"))
      (node (ref "E5") (pin "6") (pinfunction "1_6") (pintype "passive"))
      (node (ref "E5") (pin "7") (pinfunction "1_7") (pintype "passive"))
      (node (ref "E5") (pin "8") (pinfunction "1_8") (pintype "passive"))
      (node (ref "E5") (pin "9") (pinfunction "1_9") (pintype "passive"))
      (node (ref "E6") (pin "1") (pinfunction "1_1") (pintype "passive"))
      (node (ref "E6") (pin "10") (pinfunction "1_10") (pintype "passive"))
      (node (ref "E6") (pin "11") (pinfunction "1_11") (pintype "passive"))
      (node (ref "E6") (pin "12") (pinfunction "1_12") (pintype "passive"))
      (node (ref "E6") (pin "13") (pinfunction "1_13") (pintype "passive"))
      (node (ref "E6") (pin "14") (pinfunction "1_14") (pintype "passive"))
      (node (ref "E6") (pin "15") (pinfunction "1_15") (pintype "passive"))
      (node (ref "E6") (pin "16") (pinfunction "1_16") (pintype "passive"))
      (node (ref "E6") (pin "17") (pinfunction "1_17") (pintype "passive"))
      (node (ref "E6") (pin "18") (pinfunction "1_18") (pintype "passive"))
      (node (ref "E6") (pin "19") (pinfunction "1_19") (pintype "passive"))
      (node (ref "E6") (pin "2") (pinfunction "1_2") (pintype "passive"))
      (node (ref "E6") (pin "20") (pinfunction "1_20") (pintype "passive"))
      (node (ref "E6") (pin "21") (pinfunction "1_21") (pintype "passive"))
      (node (ref "E6") (pin "22") (pinfunction "1_22") (pintype "passive"))
      (node (ref "E6") (pin "23") (pinfunction "1_23") (pintype "passive"))
      (node (ref "E6") (pin "24") (pinfunction "1_24") (pintype "passive"))
      (node (ref "E6") (pin "25") (pinfunction "1_25") (pintype "passive"))
      (node (ref "E6") (pin "3") (pinfunction "1_3") (pintype "passive"))
      (node (ref "E6") (pin "4") (pinfunction "1_4") (pintype "passive"))
      (node (ref "E6") (pin "5") (pinfunction "1_5") (pintype "passive"))
      (node (ref "E6") (pin "6") (pinfunction "1_6") (pintype "passive"))
      (node (ref "E6") (pin "7") (pinfunction "1_7") (pintype "passive"))
      (node (ref "E6") (pin "8") (pinfunction "1_8") (pintype "passive"))
      (node (ref "E6") (pin "9") (pinfunction "1_9") (pintype "passive"))
      (node (ref "Q11") (pin "5") (pinfunction "D_5") (pintype "passive"))
      (node (ref "Q11") (pin "6") (pinfunction "D_6") (pintype "passive"))
      (node (ref "Q11") (pin "7") (pinfunction "D_7") (pintype "passive"))
      (node (ref "Q11") (pin "8") (pinfunction "D_8") (pintype "passive"))
      (node (ref "Q11") (pin "TH") (pinfunction "D_TH") (pintype "passive"))
      (node (ref "Q12") (pin "5") (pinfunction "D_5") (pintype "passive"))
      (node (ref "Q12") (pin "6") (pinfunction "D_6") (pintype "passive"))
      (node (ref "Q12") (pin "7") (pinfunction "D_7") (pintype "passive"))
      (node (ref "Q12") (pin "8") (pinfunction "D_8") (pintype "passive"))
      (node (ref "Q12") (pin "TH") (pinfunction "D_TH") (pintype "passive"))
      (node (ref "Q13") (pin "5") (pinfunction "D_5") (pintype "passive"))
      (node (ref "Q13") (pin "6") (pinfunction "D_6") (pintype "passive"))
      (node (ref "Q13") (pin "7") (pinfunction "D_7") (pintype "passive"))
      (node (ref "Q13") (pin "8") (pinfunction "D_8") (pintype "passive"))
      (node (ref "Q13") (pin "TH") (pinfunction "D_TH") (pintype "passive"))
      (node (ref "Q14") (pin "5") (pinfunction "D_5") (pintype "passive"))
      (node (ref "Q14") (pin "6") (pinfunction "D_6") (pintype "passive"))
      (node (ref "Q14") (pin "7") (pinfunction "D_7") (pintype "passive"))
      (node (ref "Q14") (pin "8") (pinfunction "D_8") (pintype "passive"))
      (node (ref "Q14") (pin "TH") (pinfunction "D_TH") (pintype "passive"))
      (node (ref "Q16") (pin "5") (pinfunction "D_5") (pintype "passive"))
      (node (ref "Q16") (pin "6") (pinfunction "D_6") (pintype "passive"))
      (node (ref "Q16") (pin "7") (pinfunction "D_7") (pintype "passive"))
      (node (ref "Q16") (pin "8") (pinfunction "D_8") (pintype "passive"))
      (node (ref "Q16") (pin "TH") (pinfunction "D_TH") (pintype "passive"))
      (node (ref "Q18") (pin "5") (pinfunction "D_5") (pintype "passive"))
      (node (ref "Q18") (pin "6") (pinfunction "D_6") (pintype "passive"))
      (node (ref "Q18") (pin "7") (pinfunction "D_7") (pintype "passive"))
      (node (ref "Q18") (pin "8") (pinfunction "D_8") (pintype "passive"))
      (node (ref "Q18") (pin "TH") (pinfunction "D_TH") (pintype "passive"))
      (node (ref "Q25") (pin "5") (pinfunction "D_5") (pintype "passive"))
      (node (ref "Q25") (pin "6") (pinfunction "D_6") (pintype "passive"))
      (node (ref "Q25") (pin "7") (pinfunction "D_7") (pintype "passive"))
      (node (ref "Q25") (pin "8") (pinfunction "D_8") (pintype "passive"))
      (node (ref "Q25") (pin "TH") (pinfunction "D_TH") (pintype "passive"))
      (node (ref "Q26") (pin "5") (pinfunction "D_5") (pintype "passive"))
      (node (ref "Q26") (pin "6") (pinfunction "D_6") (pintype "passive"))
      (node (ref "Q26") (pin "7") (pinfunction "D_7") (pintype "passive"))
      (node (ref "Q26") (pin "8") (pinfunction "D_8") (pintype "passive"))
      (node (ref "Q26") (pin "TH") (pinfunction "D_TH") (pintype "passive"))
      (node (ref "Q27") (pin "5") (pinfunction "D_5") (pintype "passive"))
      (node (ref "Q27") (pin "6") (pinfunction "D_6") (pintype "passive"))
      (node (ref "Q27") (pin "7") (pinfunction "D_7") (pintype "passive"))
      (node (ref "Q27") (pin "8") (pinfunction "D_8") (pintype "passive"))
      (node (ref "Q27") (pin "TH") (pinfunction "D_TH") (pintype "passive"))
      (node (ref "Q29") (pin "5") (pinfunction "D_5") (pintype "passive"))
      (node (ref "Q29") (pin "6") (pinfunction "D_6") (pintype "passive"))
      (node (ref "Q29") (pin "7") (pinfunction "D_7") (pintype "passive"))
      (node (ref "Q29") (pin "8") (pinfunction "D_8") (pintype "passive"))
      (node (ref "Q29") (pin "TH") (pinfunction "D_TH") (pintype "passive"))
      (node (ref "Q31") (pin "5") (pinfunction "D_5") (pintype "passive"))
      (node (ref "Q31") (pin "6") (pinfunction "D_6") (pintype "passive"))
      (node (ref "Q31") (pin "7") (pinfunction "D_7") (pintype "passive"))
      (node (ref "Q31") (pin "8") (pinfunction "D_8") (pintype "passive"))
      (node (ref "Q31") (pin "TH") (pinfunction "D_TH") (pintype "passive"))
      (node (ref "Q32") (pin "5") (pinfunction "D_5") (pintype "passive"))
      (node (ref "Q32") (pin "6") (pinfunction "D_6") (pintype "passive"))
      (node (ref "Q32") (pin "7") (pinfunction "D_7") (pintype "passive"))
      (node (ref "Q32") (pin "8") (pinfunction "D_8") (pintype "passive"))
      (node (ref "Q32") (pin "TH") (pinfunction "D_TH") (pintype "passive"))
      (node (ref "Q33") (pin "5") (pinfunction "D_5") (pintype "passive"))
      (node (ref "Q33") (pin "6") (pinfunction "D_6") (pintype "passive"))
      (node (ref "Q33") (pin "7") (pinfunction "D_7") (pintype "passive"))
      (node (ref "Q33") (pin "8") (pinfunction "D_8") (pintype "passive"))
      (node (ref "Q33") (pin "TH") (pinfunction "D_TH") (pintype "passive"))
      (node (ref "Q34") (pin "5") (pinfunction "D_5") (pintype "passive"))
      (node (ref "Q34") (pin "6") (pinfunction "D_6") (pintype "passive"))
      (node (ref "Q34") (pin "7") (pinfunction "D_7") (pintype "passive"))
      (node (ref "Q34") (pin "8") (pinfunction "D_8") (pintype "passive"))
      (node (ref "Q34") (pin "TH") (pinfunction "D_TH") (pintype "passive"))
      (node (ref "Q36") (pin "5") (pinfunction "D_5") (pintype "passive"))
      (node (ref "Q36") (pin "6") (pinfunction "D_6") (pintype "passive"))
      (node (ref "Q36") (pin "7") (pinfunction "D_7") (pintype "passive"))
      (node (ref "Q36") (pin "8") (pinfunction "D_8") (pintype "passive"))
      (node (ref "Q36") (pin "TH") (pinfunction "D_TH") (pintype "passive"))
      (node (ref "Q40") (pin "5") (pinfunction "D_5") (pintype "passive"))
      (node (ref "Q40") (pin "6") (pinfunction "D_6") (pintype "passive"))
      (node (ref "Q40") (pin "7") (pinfunction "D_7") (pintype "passive"))
      (node (ref "Q40") (pin "8") (pinfunction "D_8") (pintype "passive"))
      (node (ref "Q40") (pin "TH") (pinfunction "D_TH") (pintype "passive"))
      (node (ref "Q41") (pin "5") (pinfunction "D_5") (pintype "passive"))
      (node (ref "Q41") (pin "6") (pinfunction "D_6") (pintype "passive"))
      (node (ref "Q41") (pin "7") (pinfunction "D_7") (pintype "passive"))
      (node (ref "Q41") (pin "8") (pinfunction "D_8") (pintype "passive"))
      (node (ref "Q41") (pin "TH") (pinfunction "D_TH") (pintype "passive"))
      (node (ref "Q42") (pin "5") (pinfunction "D_5") (pintype "passive"))
      (node (ref "Q42") (pin "6") (pinfunction "D_6") (pintype "passive"))
      (node (ref "Q42") (pin "7") (pinfunction "D_7") (pintype "passive"))
      (node (ref "Q42") (pin "8") (pinfunction "D_8") (pintype "passive"))
      (node (ref "Q42") (pin "TH") (pinfunction "D_TH") (pintype "passive"))
      (node (ref "Q44") (pin "5") (pinfunction "D_5") (pintype "passive"))
      (node (ref "Q44") (pin "6") (pinfunction "D_6") (pintype "passive"))
      (node (ref "Q44") (pin "7") (pinfunction "D_7") (pintype "passive"))
      (node (ref "Q44") (pin "8") (pinfunction "D_8") (pintype "passive"))
      (node (ref "Q44") (pin "TH") (pinfunction "D_TH") (pintype "passive"))
      (node (ref "Q46") (pin "5") (pinfunction "D_5") (pintype "passive"))
      (node (ref "Q46") (pin "6") (pinfunction "D_6") (pintype "passive"))
      (node (ref "Q46") (pin "7") (pinfunction "D_7") (pintype "passive"))
      (node (ref "Q46") (pin "8") (pinfunction "D_8") (pintype "passive"))
      (node (ref "Q46") (pin "TH") (pinfunction "D_TH") (pintype "passive"))
      (node (ref "Q48") (pin "5") (pinfunction "D_5") (pintype "passive"))
      (node (ref "Q48") (pin "6") (pinfunction "D_6") (pintype "passive"))
      (node (ref "Q48") (pin "7") (pinfunction "D_7") (pintype "passive"))
      (node (ref "Q48") (pin "8") (pinfunction "D_8") (pintype "passive"))
      (node (ref "Q48") (pin "TH") (pinfunction "D_TH") (pintype "passive"))
      (node (ref "Q7") (pin "5") (pinfunction "D_5") (pintype "passive"))
      (node (ref "Q7") (pin "6") (pinfunction "D_6") (pintype "passive"))
      (node (ref "Q7") (pin "7") (pinfunction "D_7") (pintype "passive"))
      (node (ref "Q7") (pin "8") (pinfunction "D_8") (pintype "passive"))
      (node (ref "Q7") (pin "TH") (pinfunction "D_TH") (pintype "passive"))
      (node (ref "Q8") (pin "5") (pinfunction "D_5") (pintype "passive"))
      (node (ref "Q8") (pin "6") (pinfunction "D_6") (pintype "passive"))
      (node (ref "Q8") (pin "7") (pinfunction "D_7") (pintype "passive"))
      (node (ref "Q8") (pin "8") (pinfunction "D_8") (pintype "passive"))
      (node (ref "Q8") (pin "TH") (pinfunction "D_TH") (pintype "passive"))
      (node (ref "Q9") (pin "5") (pinfunction "D_5") (pintype "passive"))
      (node (ref "Q9") (pin "6") (pinfunction "D_6") (pintype "passive"))
      (node (ref "Q9") (pin "7") (pinfunction "D_7") (pintype "passive"))
      (node (ref "Q9") (pin "8") (pinfunction "D_8") (pintype "passive"))
      (node (ref "Q9") (pin "TH") (pinfunction "D_TH") (pintype "passive"))
    )
    (net (code "8") (name "VSS") (class "Default")
      (node (ref "E11") (pin "1") (pinfunction "1_1") (pintype "passive"))
      (node (ref "E11") (pin "10") (pinfunction "1_10") (pintype "passive"))
      (node (ref "E11") (pin "11") (pinfunction "1_11") (pintype "passive"))
      (node (ref "E11") (pin "12") (pinfunction "1_12") (pintype "passive"))
      (node (ref "E11") (pin "13") (pinfunction "1_13") (pintype "passive"))
      (node (ref "E11") (pin "14") (pinfunction "1_14") (pintype "passive"))
      (node (ref "E11") (pin "15") (pinfunction "1_15") (pintype "passive"))
      (node (ref "E11") (pin "16") (pinfunction "1_16") (pintype "passive"))
      (node (ref "E11") (pin "17") (pinfunction "1_17") (pintype "passive"))
      (node (ref "E11") (pin "18") (pinfunction "1_18") (pintype "passive"))
      (node (ref "E11") (pin "19") (pinfunction "1_19") (pintype "passive"))
      (node (ref "E11") (pin "2") (pinfunction "1_2") (pintype "passive"))
      (node (ref "E11") (pin "20") (pinfunction "1_20") (pintype "passive"))
      (node (ref "E11") (pin "21") (pinfunction "1_21") (pintype "passive"))
      (node (ref "E11") (pin "22") (pinfunction "1_22") (pintype "passive"))
      (node (ref "E11") (pin "23") (pinfunction "1_23") (pintype "passive"))
      (node (ref "E11") (pin "24") (pinfunction "1_24") (pintype "passive"))
      (node (ref "E11") (pin "25") (pinfunction "1_25") (pintype "passive"))
      (node (ref "E11") (pin "3") (pinfunction "1_3") (pintype "passive"))
      (node (ref "E11") (pin "4") (pinfunction "1_4") (pintype "passive"))
      (node (ref "E11") (pin "5") (pinfunction "1_5") (pintype "passive"))
      (node (ref "E11") (pin "6") (pinfunction "1_6") (pintype "passive"))
      (node (ref "E11") (pin "7") (pinfunction "1_7") (pintype "passive"))
      (node (ref "E11") (pin "8") (pinfunction "1_8") (pintype "passive"))
      (node (ref "E11") (pin "9") (pinfunction "1_9") (pintype "passive"))
      (node (ref "E15") (pin "1") (pinfunction "1_1") (pintype "passive"))
      (node (ref "E15") (pin "10") (pinfunction "1_10") (pintype "passive"))
      (node (ref "E15") (pin "11") (pinfunction "1_11") (pintype "passive"))
      (node (ref "E15") (pin "12") (pinfunction "1_12") (pintype "passive"))
      (node (ref "E15") (pin "13") (pinfunction "1_13") (pintype "passive"))
      (node (ref "E15") (pin "14") (pinfunction "1_14") (pintype "passive"))
      (node (ref "E15") (pin "15") (pinfunction "1_15") (pintype "passive"))
      (node (ref "E15") (pin "16") (pinfunction "1_16") (pintype "passive"))
      (node (ref "E15") (pin "17") (pinfunction "1_17") (pintype "passive"))
      (node (ref "E15") (pin "18") (pinfunction "1_18") (pintype "passive"))
      (node (ref "E15") (pin "19") (pinfunction "1_19") (pintype "passive"))
      (node (ref "E15") (pin "2") (pinfunction "1_2") (pintype "passive"))
      (node (ref "E15") (pin "20") (pinfunction "1_20") (pintype "passive"))
      (node (ref "E15") (pin "21") (pinfunction "1_21") (pintype "passive"))
      (node (ref "E15") (pin "22") (pinfunction "1_22") (pintype "passive"))
      (node (ref "E15") (pin "23") (pinfunction "1_23") (pintype "passive"))
      (node (ref "E15") (pin "24") (pinfunction "1_24") (pintype "passive"))
      (node (ref "E15") (pin "25") (pinfunction "1_25") (pintype "passive"))
      (node (ref "E15") (pin "3") (pinfunction "1_3") (pintype "passive"))
      (node (ref "E15") (pin "4") (pinfunction "1_4") (pintype "passive"))
      (node (ref "E15") (pin "5") (pinfunction "1_5") (pintype "passive"))
      (node (ref "E15") (pin "6") (pinfunction "1_6") (pintype "passive"))
      (node (ref "E15") (pin "7") (pinfunction "1_7") (pintype "passive"))
      (node (ref "E15") (pin "8") (pinfunction "1_8") (pintype "passive"))
      (node (ref "E15") (pin "9") (pinfunction "1_9") (pintype "passive"))
      (node (ref "E2") (pin "1") (pinfunction "1_1") (pintype "passive"))
      (node (ref "E2") (pin "10") (pinfunction "1_10") (pintype "passive"))
      (node (ref "E2") (pin "11") (pinfunction "1_11") (pintype "passive"))
      (node (ref "E2") (pin "12") (pinfunction "1_12") (pintype "passive"))
      (node (ref "E2") (pin "13") (pinfunction "1_13") (pintype "passive"))
      (node (ref "E2") (pin "14") (pinfunction "1_14") (pintype "passive"))
      (node (ref "E2") (pin "15") (pinfunction "1_15") (pintype "passive"))
      (node (ref "E2") (pin "16") (pinfunction "1_16") (pintype "passive"))
      (node (ref "E2") (pin "17") (pinfunction "1_17") (pintype "passive"))
      (node (ref "E2") (pin "18") (pinfunction "1_18") (pintype "passive"))
      (node (ref "E2") (pin "19") (pinfunction "1_19") (pintype "passive"))
      (node (ref "E2") (pin "2") (pinfunction "1_2") (pintype "passive"))
      (node (ref "E2") (pin "20") (pinfunction "1_20") (pintype "passive"))
      (node (ref "E2") (pin "21") (pinfunction "1_21") (pintype "passive"))
      (node (ref "E2") (pin "22") (pinfunction "1_22") (pintype "passive"))
      (node (ref "E2") (pin "23") (pinfunction "1_23") (pintype "passive"))
      (node (ref "E2") (pin "24") (pinfunction "1_24") (pintype "passive"))
      (node (ref "E2") (pin "25") (pinfunction "1_25") (pintype "passive"))
      (node (ref "E2") (pin "3") (pinfunction "1_3") (pintype "passive"))
      (node (ref "E2") (pin "4") (pinfunction "1_4") (pintype "passive"))
      (node (ref "E2") (pin "5") (pinfunction "1_5") (pintype "passive"))
      (node (ref "E2") (pin "6") (pinfunction "1_6") (pintype "passive"))
      (node (ref "E2") (pin "7") (pinfunction "1_7") (pintype "passive"))
      (node (ref "E2") (pin "8") (pinfunction "1_8") (pintype "passive"))
      (node (ref "E2") (pin "9") (pinfunction "1_9") (pintype "passive"))
      (node (ref "E7") (pin "1") (pinfunction "1_1") (pintype "passive"))
      (node (ref "E7") (pin "10") (pinfunction "1_10") (pintype "passive"))
      (node (ref "E7") (pin "11") (pinfunction "1_11") (pintype "passive"))
      (node (ref "E7") (pin "12") (pinfunction "1_12") (pintype "passive"))
      (node (ref "E7") (pin "13") (pinfunction "1_13") (pintype "passive"))
      (node (ref "E7") (pin "14") (pinfunction "1_14") (pintype "passive"))
      (node (ref "E7") (pin "15") (pinfunction "1_15") (pintype "passive"))
      (node (ref "E7") (pin "16") (pinfunction "1_16") (pintype "passive"))
      (node (ref "E7") (pin "17") (pinfunction "1_17") (pintype "passive"))
      (node (ref "E7") (pin "18") (pinfunction "1_18") (pintype "passive"))
      (node (ref "E7") (pin "19") (pinfunction "1_19") (pintype "passive"))
      (node (ref "E7") (pin "2") (pinfunction "1_2") (pintype "passive"))
      (node (ref "E7") (pin "20") (pinfunction "1_20") (pintype "passive"))
      (node (ref "E7") (pin "21") (pinfunction "1_21") (pintype "passive"))
      (node (ref "E7") (pin "22") (pinfunction "1_22") (pintype "passive"))
      (node (ref "E7") (pin "23") (pinfunction "1_23") (pintype "passive"))
      (node (ref "E7") (pin "24") (pinfunction "1_24") (pintype "passive"))
      (node (ref "E7") (pin "25") (pinfunction "1_25") (pintype "passive"))
      (node (ref "E7") (pin "3") (pinfunction "1_3") (pintype "passive"))
      (node (ref "E7") (pin "4") (pinfunction "1_4") (pintype "passive"))
      (node (ref "E7") (pin "5") (pinfunction "1_5") (pintype "passive"))
      (node (ref "E7") (pin "6") (pinfunction "1_6") (pintype "passive"))
      (node (ref "E7") (pin "7") (pinfunction "1_7") (pintype "passive"))
      (node (ref "E7") (pin "8") (pinfunction "1_8") (pintype "passive"))
      (node (ref "E7") (pin "9") (pinfunction "1_9") (pintype "passive"))
      (node (ref "Q1") (pin "1") (pinfunction "S_1") (pintype "passive"))
      (node (ref "Q1") (pin "2") (pinfunction "S_2") (pintype "passive"))
      (node (ref "Q1") (pin "3") (pinfunction "S_3") (pintype "passive"))
      (node (ref "Q10") (pin "1") (pinfunction "S_1") (pintype "passive"))
      (node (ref "Q10") (pin "2") (pinfunction "S_2") (pintype "passive"))
      (node (ref "Q10") (pin "3") (pinfunction "S_3") (pintype "passive"))
      (node (ref "Q15") (pin "1") (pinfunction "S_1") (pintype "passive"))
      (node (ref "Q15") (pin "2") (pinfunction "S_2") (pintype "passive"))
      (node (ref "Q15") (pin "3") (pinfunction "S_3") (pintype "passive"))
      (node (ref "Q17") (pin "1") (pinfunction "S_1") (pintype "passive"))
      (node (ref "Q17") (pin "2") (pinfunction "S_2") (pintype "passive"))
      (node (ref "Q17") (pin "3") (pinfunction "S_3") (pintype "passive"))
      (node (ref "Q19") (pin "1") (pinfunction "S_1") (pintype "passive"))
      (node (ref "Q19") (pin "2") (pinfunction "S_2") (pintype "passive"))
      (node (ref "Q19") (pin "3") (pinfunction "S_3") (pintype "passive"))
      (node (ref "Q2") (pin "1") (pinfunction "S_1") (pintype "passive"))
      (node (ref "Q2") (pin "2") (pinfunction "S_2") (pintype "passive"))
      (node (ref "Q2") (pin "3") (pinfunction "S_3") (pintype "passive"))
      (node (ref "Q20") (pin "1") (pinfunction "S_1") (pintype "passive"))
      (node (ref "Q20") (pin "2") (pinfunction "S_2") (pintype "passive"))
      (node (ref "Q20") (pin "3") (pinfunction "S_3") (pintype "passive"))
      (node (ref "Q21") (pin "1") (pinfunction "S_1") (pintype "passive"))
      (node (ref "Q21") (pin "2") (pinfunction "S_2") (pintype "passive"))
      (node (ref "Q21") (pin "3") (pinfunction "S_3") (pintype "passive"))
      (node (ref "Q22") (pin "1") (pinfunction "S_1") (pintype "passive"))
      (node (ref "Q22") (pin "2") (pinfunction "S_2") (pintype "passive"))
      (node (ref "Q22") (pin "3") (pinfunction "S_3") (pintype "passive"))
      (node (ref "Q23") (pin "1") (pinfunction "S_1") (pintype "passive"))
      (node (ref "Q23") (pin "2") (pinfunction "S_2") (pintype "passive"))
      (node (ref "Q23") (pin "3") (pinfunction "S_3") (pintype "passive"))
      (node (ref "Q24") (pin "1") (pinfunction "S_1") (pintype "passive"))
      (node (ref "Q24") (pin "2") (pinfunction "S_2") (pintype "passive"))
      (node (ref "Q24") (pin "3") (pinfunction "S_3") (pintype "passive"))
      (node (ref "Q28") (pin "1") (pinfunction "S_1") (pintype "passive"))
      (node (ref "Q28") (pin "2") (pinfunction "S_2") (pintype "passive"))
      (node (ref "Q28") (pin "3") (pinfunction "S_3") (pintype "passive"))
      (node (ref "Q3") (pin "1") (pinfunction "S_1") (pintype "passive"))
      (node (ref "Q3") (pin "2") (pinfunction "S_2") (pintype "passive"))
      (node (ref "Q3") (pin "3") (pinfunction "S_3") (pintype "passive"))
      (node (ref "Q30") (pin "1") (pinfunction "S_1") (pintype "passive"))
      (node (ref "Q30") (pin "2") (pinfunction "S_2") (pintype "passive"))
      (node (ref "Q30") (pin "3") (pinfunction "S_3") (pintype "passive"))
      (node (ref "Q35") (pin "1") (pinfunction "S_1") (pintype "passive"))
      (node (ref "Q35") (pin "2") (pinfunction "S_2") (pintype "passive"))
      (node (ref "Q35") (pin "3") (pinfunction "S_3") (pintype "passive"))
      (node (ref "Q37") (pin "1") (pinfunction "S_1") (pintype "passive"))
      (node (ref "Q37") (pin "2") (pinfunction "S_2") (pintype "passive"))
      (node (ref "Q37") (pin "3") (pinfunction "S_3") (pintype "passive"))
      (node (ref "Q38") (pin "1") (pinfunction "S_1") (pintype "passive"))
      (node (ref "Q38") (pin "2") (pinfunction "S_2") (pintype "passive"))
      (node (ref "Q38") (pin "3") (pinfunction "S_3") (pintype "passive"))
      (node (ref "Q39") (pin "1") (pinfunction "S_1") (pintype "passive"))
      (node (ref "Q39") (pin "2") (pinfunction "S_2") (pintype "passive"))
      (node (ref "Q39") (pin "3") (pinfunction "S_3") (pintype "passive"))
      (node (ref "Q4") (pin "1") (pinfunction "S_1") (pintype "passive"))
      (node (ref "Q4") (pin "2") (pinfunction "S_2") (pintype "passive"))
      (node (ref "Q4") (pin "3") (pinfunction "S_3") (pintype "passive"))
      (node (ref "Q43") (pin "1") (pinfunction "S_1") (pintype "passive"))
      (node (ref "Q43") (pin "2") (pinfunction "S_2") (pintype "passive"))
      (node (ref "Q43") (pin "3") (pinfunction "S_3") (pintype "passive"))
      (node (ref "Q45") (pin "1") (pinfunction "S_1") (pintype "passive"))
      (node (ref "Q45") (pin "2") (pinfunction "S_2") (pintype "passive"))
      (node (ref "Q45") (pin "3") (pinfunction "S_3") (pintype "passive"))
      (node (ref "Q47") (pin "1") (pinfunction "S_1") (pintype "passive"))
      (node (ref "Q47") (pin "2") (pinfunction "S_2") (pintype "passive"))
      (node (ref "Q47") (pin "3") (pinfunction "S_3") (pintype "passive"))
      (node (ref "Q5") (pin "1") (pinfunction "S_1") (pintype "passive"))
      (node (ref "Q5") (pin "2") (pinfunction "S_2") (pintype "passive"))
      (node (ref "Q5") (pin "3") (pinfunction "S_3") (pintype "passive"))
      (node (ref "Q6") (pin "1") (pinfunction "S_1") (pintype "passive"))
      (node (ref "Q6") (pin "2") (pinfunction "S_2") (pintype "passive"))
      (node (ref "Q6") (pin "3") (pinfunction "S_3") (pintype "passive"))
    )
  )
)
